# interface.net
KiCad netlist of a schematic drawn in Altium Designer
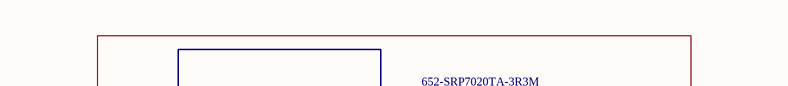
[diagram p0: interface.SchDoc, top left]
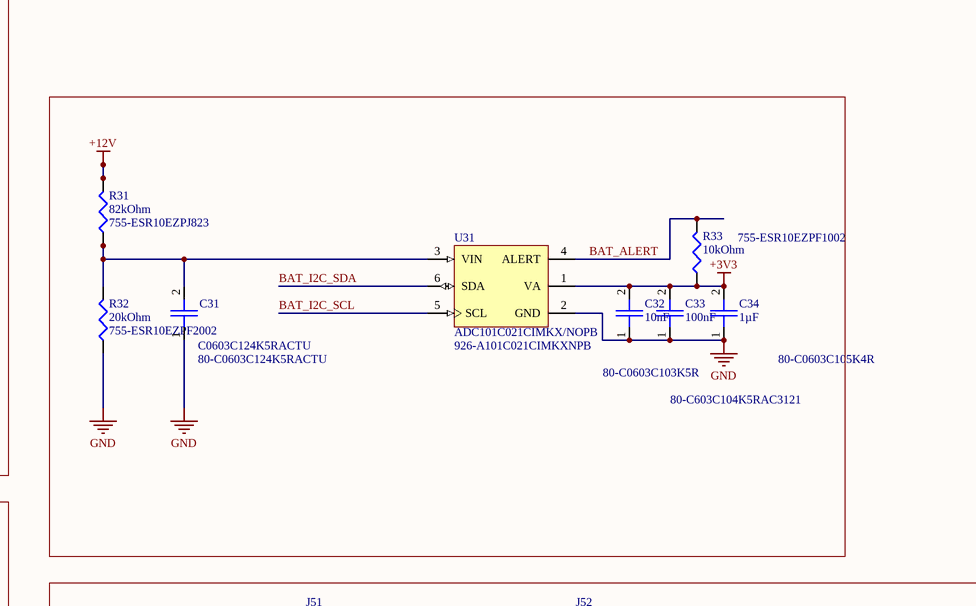
[diagram p1: interface.SchDoc, top right]
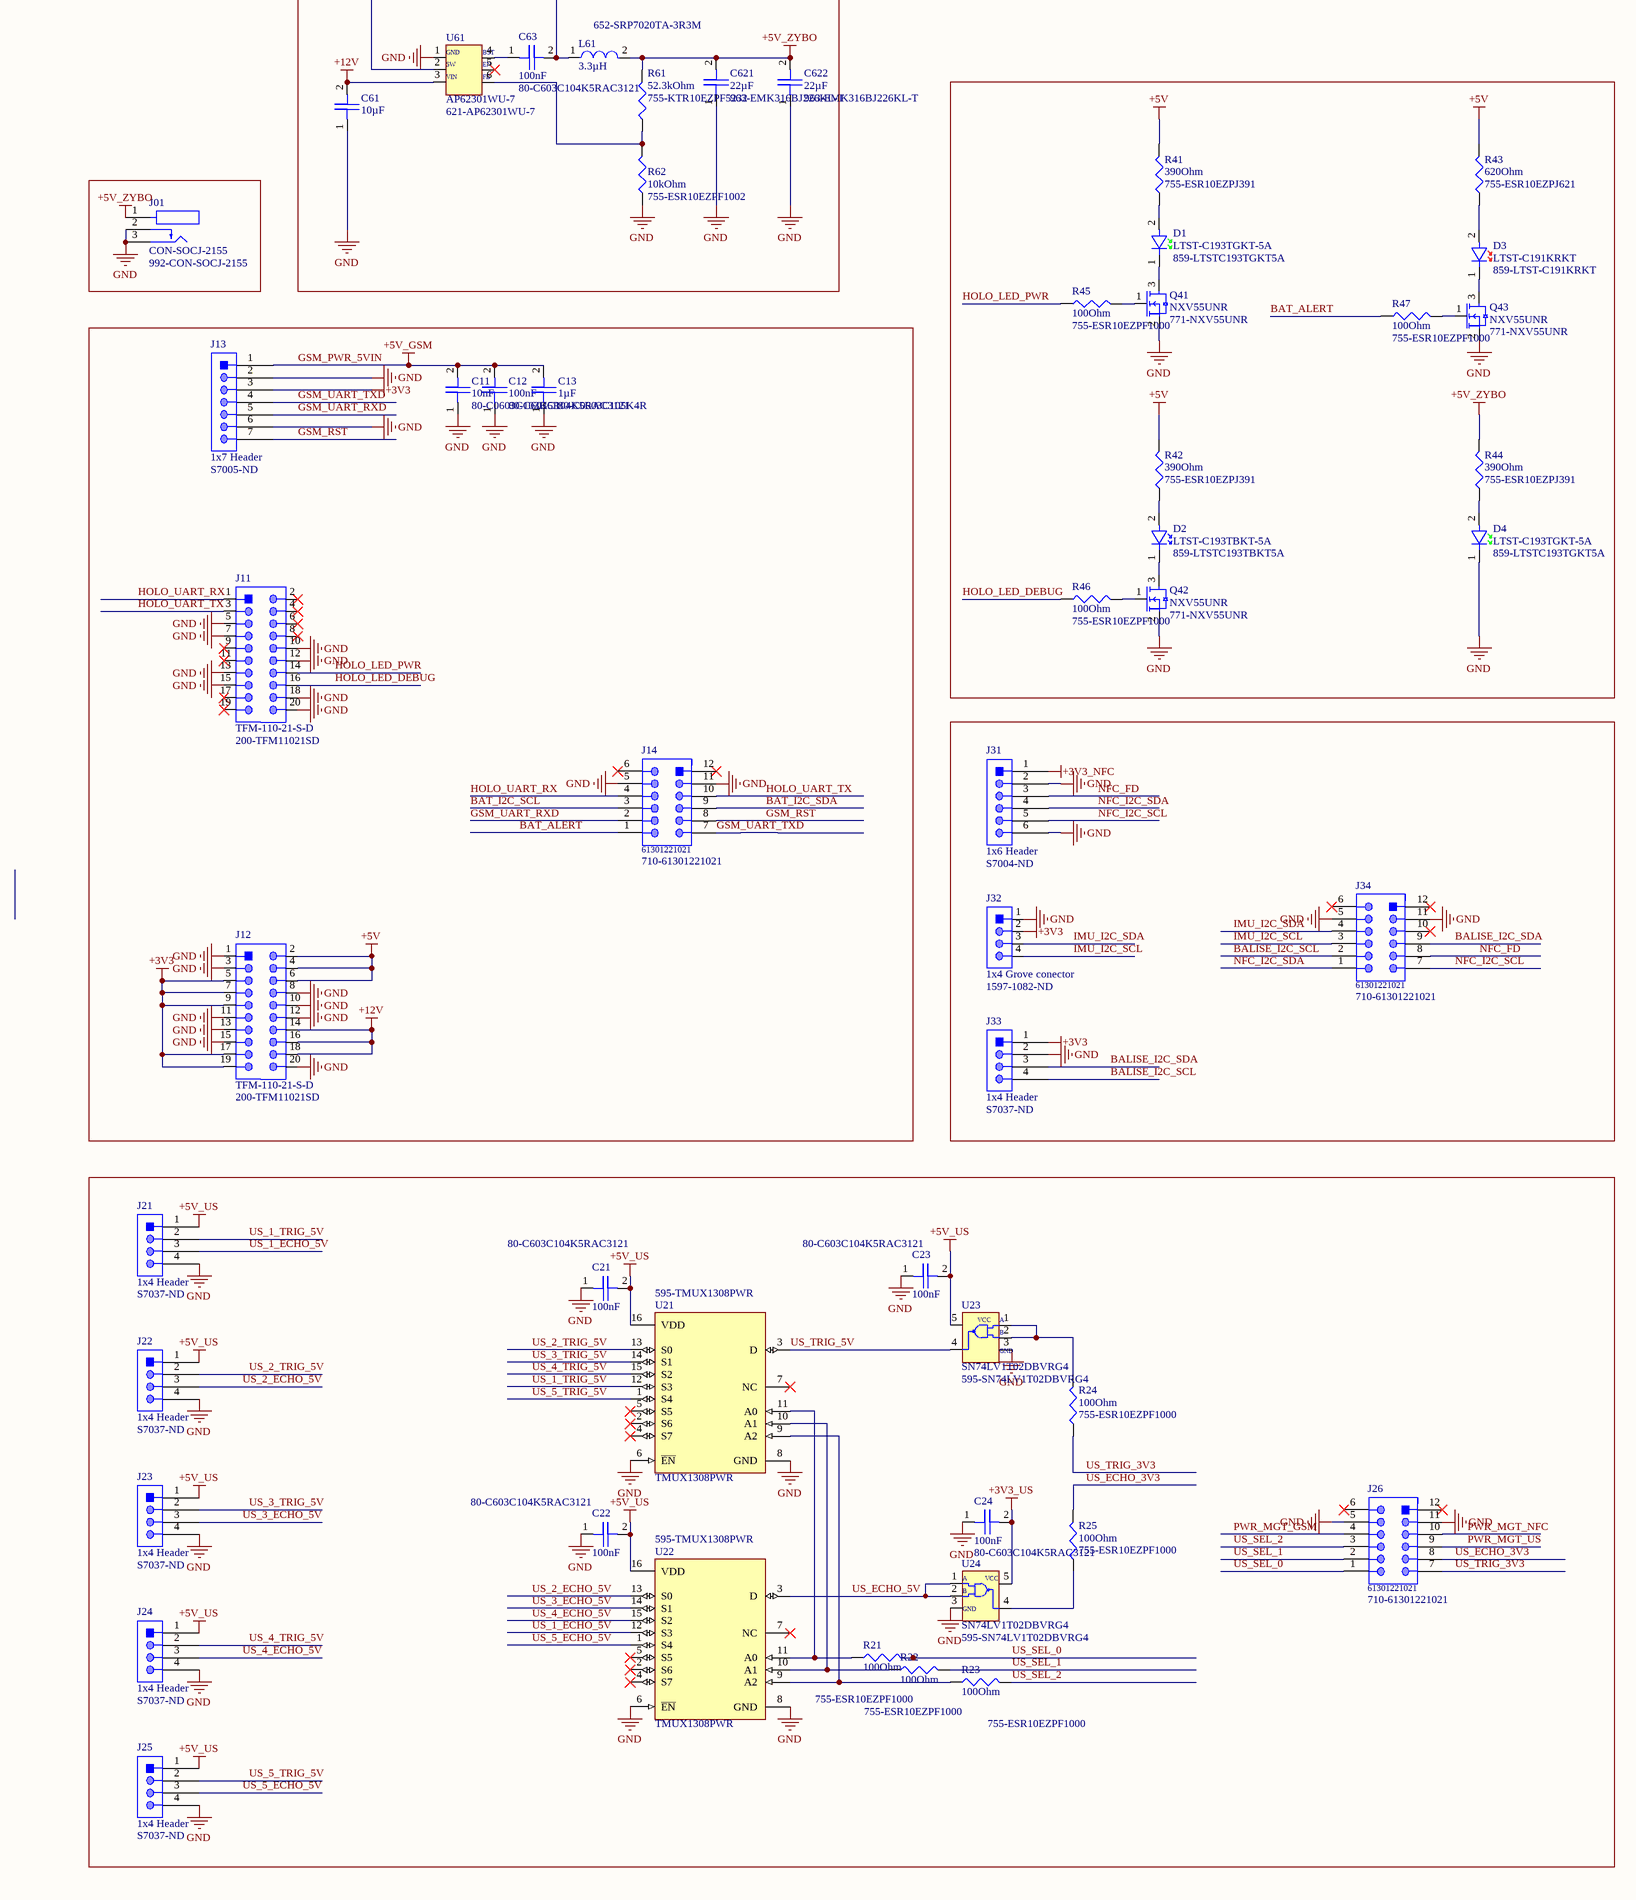
[diagram p2: interface.SchDoc, bottom left]
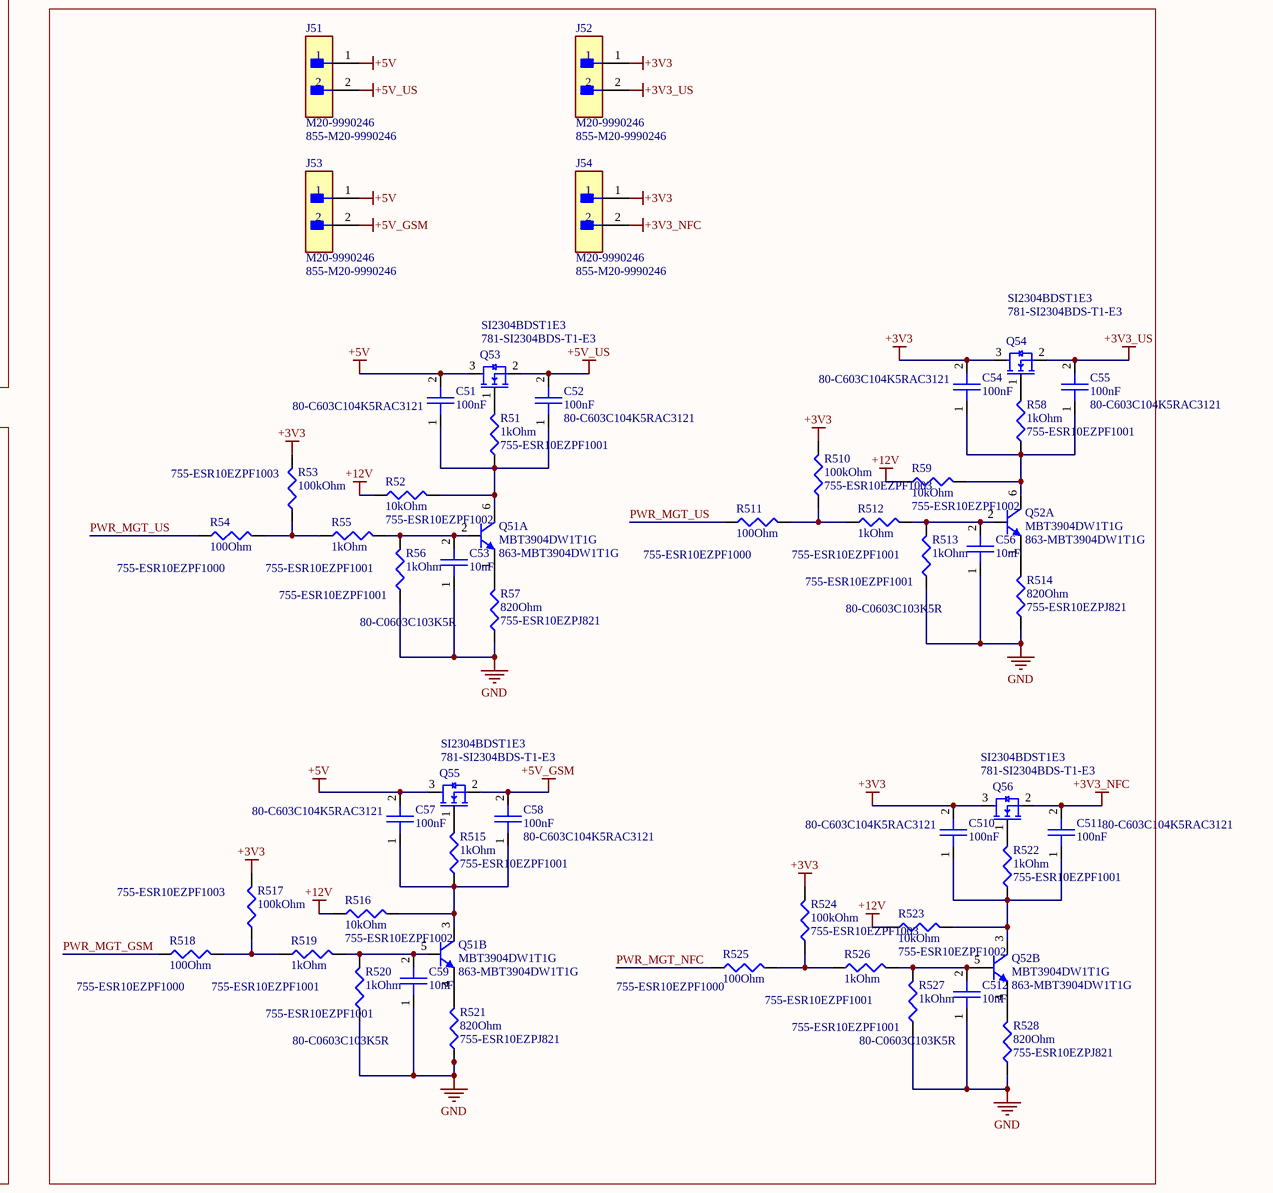
[diagram p3: interface.SchDoc, bottom right]

(export (version "E")
  (design (tool "Eeschema 10.0.6"))
  (components
    (comp (ref "C11")
      (value "10nF")
      (footprint "FP-C0603C-CF-IPC_A")
      (description "CAP CER 10000PF 50V X7R 0603")
      (fields
        (field (name "MANUFACTURER") "KEMET")
        (field (name "MANUFACTURER PART NUMBER") "C0603C103K5RACTU")
        (field (name "SUPPLIER PART NUMBER 1") "80-C0603C103K5R")
      )
      (libsource (lib "interface_Schlib") (part "C0603C103K5RACTU"))
    )
    (comp (ref "C12")
      (value "100nF")
      (footprint "FP-C0603C104K5RAC3121-IPC_A")
      (description "Cap Ceramic 0.1uF 50V X7R 10% Pad SMD 0603 125°C T/R")
      (fields
        (field (name "MANUFACTURER") "KEMET")
        (field (name "MANUFACTURER PART NUMBER") "C0603C104K5RAC3121")
        (field (name "SUPPLIER PART NUMBER 1") "80-C603C104K5RAC3121")
      )
      (libsource (lib "interface_Schlib") (part "C0603C104K5RAC3121"))
    )
    (comp (ref "C13")
      (value "1µF")
      (footprint "CAPC1608X90X35NL15T15")
      (description "Cap Ceramic 1uF 16V X7R 10% SMD 0603 125°C Paper T/R")
      (fields
        (field (name "MANUFACTURER") "KEMET")
        (field (name "MANUFACTURER PART NUMBER") "C0603C105K4RACTU")
        (field (name "SUPPLIER PART NUMBER 1") "80-C0603C105K4R")
      )
      (libsource (lib "interface_Schlib") (part "C0603C105K4RACTU"))
    )
    (comp (ref "C21")
      (value "100nF")
      (footprint "FP-C0603C104K5RAC3121-IPC_A")
      (description "Cap Ceramic 0.1uF 50V X7R 10% Pad SMD 0603 125°C T/R")
      (fields
        (field (name "MANUFACTURER") "KEMET")
        (field (name "MANUFACTURER PART NUMBER") "C0603C104K5RAC3121")
        (field (name "SUPPLIER PART NUMBER 1") "80-C603C104K5RAC3121")
      )
      (libsource (lib "interface_Schlib") (part "C0603C104K5RAC3121"))
    )
    (comp (ref "C22")
      (value "100nF")
      (footprint "FP-C0603C104K5RAC3121-IPC_A")
      (description "Cap Ceramic 0.1uF 50V X7R 10% Pad SMD 0603 125°C T/R")
      (fields
        (field (name "MANUFACTURER") "KEMET")
        (field (name "MANUFACTURER PART NUMBER") "C0603C104K5RAC3121")
        (field (name "SUPPLIER PART NUMBER 1") "80-C603C104K5RAC3121")
      )
      (libsource (lib "interface_Schlib") (part "C0603C104K5RAC3121"))
    )
    (comp (ref "C23")
      (value "100nF")
      (footprint "FP-C0603C104K5RAC3121-IPC_A")
      (description "Cap Ceramic 0.1uF 50V X7R 10% Pad SMD 0603 125°C T/R")
      (fields
        (field (name "MANUFACTURER") "KEMET")
        (field (name "MANUFACTURER PART NUMBER") "C0603C104K5RAC3121")
        (field (name "SUPPLIER PART NUMBER 1") "80-C603C104K5RAC3121")
      )
      (libsource (lib "interface_Schlib") (part "C0603C104K5RAC3121"))
    )
    (comp (ref "C24")
      (value "100nF")
      (footprint "FP-C0603C104K5RAC3121-IPC_A")
      (description "Cap Ceramic 0.1uF 50V X7R 10% Pad SMD 0603 125°C T/R")
      (fields
        (field (name "MANUFACTURER") "KEMET")
        (field (name "MANUFACTURER PART NUMBER") "C0603C104K5RAC3121")
        (field (name "SUPPLIER PART NUMBER 1") "80-C603C104K5RAC3121")
      )
      (libsource (lib "interface_Schlib") (part "C0603C104K5RAC3121"))
    )
    (comp (ref "C31")
      (value "C0603C124K5RACTU")
      (footprint "FP-C0603C-CF-IPC_A")
      (description "0603 C 120nF Ceramic Multilayer Capacitor; 50 V; +125degC; X7R Dielec; +/-10%")
      (fields
        (field (name "MANUFACTURER") "KEMET")
        (field (name "TOLERANCE") "10%")
        (field (name "SUPPLIER PART NUMBER 1") "80-C0603C124K5RACTU")
      )
      (libsource (lib "interface_Schlib") (part "C0603C124K5RACTU"))
    )
    (comp (ref "C32")
      (value "10nF")
      (footprint "FP-C0603C-CF-IPC_A")
      (description "CAP CER 10000PF 50V X7R 0603")
      (fields
        (field (name "MANUFACTURER") "KEMET")
        (field (name "MANUFACTURER PART NUMBER") "C0603C103K5RACTU")
        (field (name "SUPPLIER PART NUMBER 1") "80-C0603C103K5R")
      )
      (libsource (lib "interface_Schlib") (part "C0603C103K5RACTU"))
    )
    (comp (ref "C33")
      (value "100nF")
      (footprint "FP-C0603C104K5RAC3121-IPC_A")
      (description "Cap Ceramic 0.1uF 50V X7R 10% Pad SMD 0603 125°C T/R")
      (fields
        (field (name "MANUFACTURER") "KEMET")
        (field (name "MANUFACTURER PART NUMBER") "C0603C104K5RAC3121")
        (field (name "SUPPLIER PART NUMBER 1") "80-C603C104K5RAC3121")
      )
      (libsource (lib "interface_Schlib") (part "C0603C104K5RAC3121"))
    )
    (comp (ref "C34")
      (value "1µF")
      (footprint "CAPC1608X90X35NL15T15")
      (description "Cap Ceramic 1uF 16V X7R 10% SMD 0603 125°C Paper T/R")
      (fields
        (field (name "MANUFACTURER") "KEMET")
        (field (name "MANUFACTURER PART NUMBER") "C0603C105K4RACTU")
        (field (name "SUPPLIER PART NUMBER 1") "80-C0603C105K4R")
      )
      (libsource (lib "interface_Schlib") (part "C0603C105K4RACTU"))
    )
    (comp (ref "C51")
      (value "100nF")
      (footprint "FP-C0603C104K5RAC3121-IPC_A")
      (description "Cap Ceramic 0.1uF 50V X7R 10% Pad SMD 0603 125°C T/R")
      (fields
        (field (name "MANUFACTURER") "KEMET")
        (field (name "MANUFACTURER PART NUMBER") "C0603C104K5RAC3121")
        (field (name "SUPPLIER PART NUMBER 1") "80-C603C104K5RAC3121")
      )
      (libsource (lib "interface_Schlib") (part "C0603C104K5RAC3121"))
    )
    (comp (ref "C52")
      (value "100nF")
      (footprint "FP-C0603C104K5RAC3121-IPC_A")
      (description "Cap Ceramic 0.1uF 50V X7R 10% Pad SMD 0603 125°C T/R")
      (fields
        (field (name "MANUFACTURER") "KEMET")
        (field (name "MANUFACTURER PART NUMBER") "C0603C104K5RAC3121")
        (field (name "SUPPLIER PART NUMBER 1") "80-C603C104K5RAC3121")
      )
      (libsource (lib "interface_Schlib") (part "C0603C104K5RAC3121"))
    )
    (comp (ref "C53")
      (value "10nF")
      (footprint "FP-C0603C-CF-IPC_A")
      (description "CAP CER 10000PF 50V X7R 0603")
      (fields
        (field (name "MANUFACTURER") "KEMET")
        (field (name "MANUFACTURER PART NUMBER") "C0603C103K5RACTU")
        (field (name "SUPPLIER PART NUMBER 1") "80-C0603C103K5R")
      )
      (libsource (lib "interface_Schlib") (part "C0603C103K5RACTU"))
    )
    (comp (ref "C54")
      (value "100nF")
      (footprint "FP-C0603C104K5RAC3121-IPC_A")
      (description "Cap Ceramic 0.1uF 50V X7R 10% Pad SMD 0603 125°C T/R")
      (fields
        (field (name "MANUFACTURER") "KEMET")
        (field (name "MANUFACTURER PART NUMBER") "C0603C104K5RAC3121")
        (field (name "SUPPLIER PART NUMBER 1") "80-C603C104K5RAC3121")
      )
      (libsource (lib "interface_Schlib") (part "C0603C104K5RAC3121"))
    )
    (comp (ref "C55")
      (value "100nF")
      (footprint "FP-C0603C104K5RAC3121-IPC_A")
      (description "Cap Ceramic 0.1uF 50V X7R 10% Pad SMD 0603 125°C T/R")
      (fields
        (field (name "MANUFACTURER") "KEMET")
        (field (name "MANUFACTURER PART NUMBER") "C0603C104K5RAC3121")
        (field (name "SUPPLIER PART NUMBER 1") "80-C603C104K5RAC3121")
      )
      (libsource (lib "interface_Schlib") (part "C0603C104K5RAC3121"))
    )
    (comp (ref "C56")
      (value "10nF")
      (footprint "FP-C0603C-CF-IPC_A")
      (description "CAP CER 10000PF 50V X7R 0603")
      (fields
        (field (name "MANUFACTURER") "KEMET")
        (field (name "MANUFACTURER PART NUMBER") "C0603C103K5RACTU")
        (field (name "SUPPLIER PART NUMBER 1") "80-C0603C103K5R")
      )
      (libsource (lib "interface_Schlib") (part "C0603C103K5RACTU"))
    )
    (comp (ref "C57")
      (value "100nF")
      (footprint "FP-C0603C104K5RAC3121-IPC_A")
      (description "Cap Ceramic 0.1uF 50V X7R 10% Pad SMD 0603 125°C T/R")
      (fields
        (field (name "MANUFACTURER") "KEMET")
        (field (name "MANUFACTURER PART NUMBER") "C0603C104K5RAC3121")
        (field (name "SUPPLIER PART NUMBER 1") "80-C603C104K5RAC3121")
      )
      (libsource (lib "interface_Schlib") (part "C0603C104K5RAC3121"))
    )
    (comp (ref "C58")
      (value "100nF")
      (footprint "FP-C0603C104K5RAC3121-IPC_A")
      (description "Cap Ceramic 0.1uF 50V X7R 10% Pad SMD 0603 125°C T/R")
      (fields
        (field (name "MANUFACTURER") "KEMET")
        (field (name "MANUFACTURER PART NUMBER") "C0603C104K5RAC3121")
        (field (name "SUPPLIER PART NUMBER 1") "80-C603C104K5RAC3121")
      )
      (libsource (lib "interface_Schlib") (part "C0603C104K5RAC3121"))
    )
    (comp (ref "C59")
      (value "10nF")
      (footprint "FP-C0603C-CF-IPC_A")
      (description "CAP CER 10000PF 50V X7R 0603")
      (fields
        (field (name "MANUFACTURER") "KEMET")
        (field (name "MANUFACTURER PART NUMBER") "C0603C103K5RACTU")
        (field (name "SUPPLIER PART NUMBER 1") "80-C0603C103K5R")
      )
      (libsource (lib "interface_Schlib") (part "C0603C103K5RACTU"))
    )
    (comp (ref "C61")
      (value "10µF")
      (footprint "FP-1206-L_3_2_0_15-W_1_6-IPC_A")
      (description "Capacitor Ceramic 10uF 16V X5R 10% SMD 1206 85°C Embossed T/R")
      (fields
        (field (name "MANUFACTURER") "Taiyo Yuden")
        (field (name "MANUFACTURER PART NUMBER") "EMK316BJ106KL8T")
      )
      (libsource (lib "interface_Schlib") (part "EMK316BJ106KL8T"))
    )
    (comp (ref "C63")
      (value "100nF")
      (footprint "FP-C0603C104K5RAC3121-IPC_A")
      (description "Cap Ceramic 0.1uF 50V X7R 10% Pad SMD 0603 125°C T/R")
      (fields
        (field (name "MANUFACTURER") "KEMET")
        (field (name "MANUFACTURER PART NUMBER") "C0603C104K5RAC3121")
        (field (name "SUPPLIER PART NUMBER 1") "80-C603C104K5RAC3121")
      )
      (libsource (lib "interface_Schlib") (part "C0603C104K5RAC3121"))
    )
    (comp (ref "C510")
      (value "100nF")
      (footprint "FP-C0603C104K5RAC3121-IPC_A")
      (description "Cap Ceramic 0.1uF 50V X7R 10% Pad SMD 0603 125°C T/R")
      (fields
        (field (name "MANUFACTURER") "KEMET")
        (field (name "MANUFACTURER PART NUMBER") "C0603C104K5RAC3121")
        (field (name "SUPPLIER PART NUMBER 1") "80-C603C104K5RAC3121")
      )
      (libsource (lib "interface_Schlib") (part "C0603C104K5RAC3121"))
    )
    (comp (ref "C511")
      (value "100nF")
      (footprint "FP-C0603C104K5RAC3121-IPC_A")
      (description "Cap Ceramic 0.1uF 50V X7R 10% Pad SMD 0603 125°C T/R")
      (fields
        (field (name "MANUFACTURER") "KEMET")
        (field (name "MANUFACTURER PART NUMBER") "C0603C104K5RAC3121")
        (field (name "SUPPLIER PART NUMBER 1") "80-C603C104K5RAC3121")
      )
      (libsource (lib "interface_Schlib") (part "C0603C104K5RAC3121"))
    )
    (comp (ref "C512")
      (value "10nF")
      (footprint "FP-C0603C-CF-IPC_A")
      (description "CAP CER 10000PF 50V X7R 0603")
      (fields
        (field (name "MANUFACTURER") "KEMET")
        (field (name "MANUFACTURER PART NUMBER") "C0603C103K5RACTU")
        (field (name "SUPPLIER PART NUMBER 1") "80-C0603C103K5R")
      )
      (libsource (lib "interface_Schlib") (part "C0603C103K5RACTU"))
    )
    (comp (ref "C621")
      (value "22µF")
      (footprint "CAPC3216X180N")
      (description "Cap Ceramic 22uF 16V X7R 10% SMD 0805 125°C Paper T/R")
      (fields
        (field (name "MANUFACTURER") "Taiyo Yuden")
        (field (name "MANUFACTURER PART NUMBER") "EMK316BJ226KL-T")
        (field (name "SUPPLIER PART NUMBER 1") "963-EMK316BJ226KL-T")
      )
      (libsource (lib "interface_Schlib") (part "EMK316BJ226KL-T"))
    )
    (comp (ref "C622")
      (value "22µF")
      (footprint "CAPC3216X180N")
      (description "Cap Ceramic 22uF 16V X7R 10% SMD 0805 125°C Paper T/R")
      (fields
        (field (name "MANUFACTURER") "Taiyo Yuden")
        (field (name "MANUFACTURER PART NUMBER") "EMK316BJ226KL-T")
        (field (name "SUPPLIER PART NUMBER 1") "963-EMK316BJ226KL-T")
      )
      (libsource (lib "interface_Schlib") (part "EMK316BJ226KL-T"))
    )
    (comp (ref "D1")
      (value "LTST-C193TGKT-5A")
      (footprint "FP-LTST-C193TGKT-5A")
      (description "0603(H=0.35mm) 绿色 λD=520nm~535nm VR=5V VF=2.5V~3.1V IF=5mA PD=76mW")
      (fields
        (field (name "MANUFACTURER") "Vishay Lite-On")
        (field (name "SUPPLIER PART NUMBER 1") "859-LTSTC193TGKT5A")
      )
      (libsource (lib "interface_Schlib") (part "LTST-C193TGKT-5A"))
    )
    (comp (ref "D2")
      (value "LTST-C193TBKT-5A")
      (footprint "FP-LTST-C193TBKT-5A-MFG")
      (description "0603(H=0.35mm) 蓝色 λD=465nm~475nm VR=5V VF=2.65V~3.05V IF=5mA PD=76mW")
      (fields
        (field (name "MANUFACTURER") "Vishay Lite-On")
        (field (name "SUPPLIER PART NUMBER 1") "859-LTSTC193TBKT5A")
      )
      (libsource (lib "interface_Schlib") (part "LTST-C193TBKT-5A"))
    )
    (comp (ref "D3")
      (value "LTST-C191KRKT")
      (footprint "FP-LTST-C191KRKT")
      (description "0603(H=0.65mm) 红色 λD=631nm VR=5V VF=2.0V~2.4V IF=20mA PD=75mW")
      (fields
        (field (name "MANUFACTURER") "Vishay Lite-On")
        (field (name "SUPPLIER PART NUMBER 1") "859-LTST-C191KRKT")
        (field (name "VOLTAGE") "2V")
      )
      (libsource (lib "interface_Schlib") (part "LTST-C191KRKT"))
    )
    (comp (ref "D4")
      (value "LTST-C193TGKT-5A")
      (footprint "FP-LTST-C193TGKT-5A")
      (description "0603(H=0.35mm) 绿色 λD=520nm~535nm VR=5V VF=2.5V~3.1V IF=5mA PD=76mW")
      (fields
        (field (name "MANUFACTURER") "Vishay Lite-On")
        (field (name "SUPPLIER PART NUMBER 1") "859-LTSTC193TGKT5A")
      )
      (libsource (lib "interface_Schlib") (part "LTST-C193TGKT-5A"))
    )
    (comp (ref "J01")
      (value "CON-SOCJ-2155")
      (footprint "GRAVITECH_CON-SOCJ-2155")
      (description "DC Power Connectors Power Jack/Connector 2.1mm x 5.5mm")
      (fields
        (field (name "MANUFACTURER") "Gravitech")
        (field (name "SUPPLIER PART NUMBER 1") "992-CON-SOCJ-2155")
      )
      (libsource (lib "interface_Schlib") (part "CON-SOCJ-2155"))
    )
    (comp (ref "J11")
      (value "TFM-110-21-S-D")
      (footprint "SAMTEC_TFM-110-21-S-D")
      (fields (field (name "MANUFACTURER") "Samtec") (field (name "SUPPLIER PART NUMBER 1") "200-TFM11021SD"))
      (libsource (lib "interface_Schlib") (part "TFM-110-21-S-D"))
    )
    (comp (ref "J12")
      (value "TFM-110-21-S-D")
      (footprint "SAMTEC_TFM-110-21-S-D")
      (fields (field (name "MANUFACTURER") "Samtec") (field (name "SUPPLIER PART NUMBER 1") "200-TFM11021SD"))
      (libsource (lib "interface_Schlib") (part "TFM-110-21-S-D"))
    )
    (comp (ref "J13")
      (value "1x7 Header")
      (footprint "header 1x7")
      (description "Female, 7C, Straight, .100\"CC; 3.20mm Tail, No Mt. 100u\" Tin; PBT, Phos Bronze, 105 C")
      (fields
        (field (name "MANUFACTURER") "Sullins")
        (field (name "MANUFACTURER PART NUMBER") "PPTC071LFBN-RC")
        (field (name "SUPPLIER PART NUMBER 1") "S7005-ND")
      )
      (libsource (lib "interface_Schlib") (part "PPTC071LFBN-RC"))
    )
    (comp (ref "J14")
      (value "61301221021")
      (footprint "61301221021")
      (description "THT Angled Pin Header WR-PHD, Pitch 2.54 mm, Dual Row, 12 pins")
      (fields
        (field (name "MANUFACTURER") "Wurth Elektronik")
        (field (name "SUPPLIER PART NUMBER 1") "710-61301221021")
        (field (name "PUBLISHER") "WurthElektronik")
      )
      (libsource (lib "interface_Schlib") (part "61301221021"))
    )
    (comp (ref "J21")
      (value "1x4 Header")
      (footprint "header 1x4")
      (description "4 Positions Embase Connecteur 0,100 po (2,54mm) Trou traversant Or")
      (fields
        (field (name "MANUFACTURER") "Sullins")
        (field (name "MANUFACTURER PART NUMBER") "PPPC041LFBN-RC")
        (field (name "SUPPLIER PART NUMBER 1") "S7037-ND")
      )
      (libsource (lib "interface_Schlib") (part "PPPC041LFBN-RC"))
    )
    (comp (ref "J22")
      (value "1x4 Header")
      (footprint "header 1x4")
      (description "4 Positions Embase Connecteur 0,100 po (2,54mm) Trou traversant Or")
      (fields
        (field (name "MANUFACTURER") "Sullins")
        (field (name "MANUFACTURER PART NUMBER") "PPPC041LFBN-RC")
        (field (name "SUPPLIER PART NUMBER 1") "S7037-ND")
      )
      (libsource (lib "interface_Schlib") (part "PPPC041LFBN-RC"))
    )
    (comp (ref "J23")
      (value "1x4 Header")
      (footprint "header 1x4")
      (description "4 Positions Embase Connecteur 0,100 po (2,54mm) Trou traversant Or")
      (fields
        (field (name "MANUFACTURER") "Sullins")
        (field (name "MANUFACTURER PART NUMBER") "PPPC041LFBN-RC")
        (field (name "SUPPLIER PART NUMBER 1") "S7037-ND")
      )
      (libsource (lib "interface_Schlib") (part "PPPC041LFBN-RC"))
    )
    (comp (ref "J24")
      (value "1x4 Header")
      (footprint "header 1x4")
      (description "4 Positions Embase Connecteur 0,100 po (2,54mm) Trou traversant Or")
      (fields
        (field (name "MANUFACTURER") "Sullins")
        (field (name "MANUFACTURER PART NUMBER") "PPPC041LFBN-RC")
        (field (name "SUPPLIER PART NUMBER 1") "S7037-ND")
      )
      (libsource (lib "interface_Schlib") (part "PPPC041LFBN-RC"))
    )
    (comp (ref "J25")
      (value "1x4 Header")
      (footprint "header 1x4")
      (description "4 Positions Embase Connecteur 0,100 po (2,54mm) Trou traversant Or")
      (fields
        (field (name "MANUFACTURER") "Sullins")
        (field (name "MANUFACTURER PART NUMBER") "PPPC041LFBN-RC")
        (field (name "SUPPLIER PART NUMBER 1") "S7037-ND")
      )
      (libsource (lib "interface_Schlib") (part "PPPC041LFBN-RC"))
    )
    (comp (ref "J26")
      (value "61301221021")
      (footprint "61301221021")
      (description "THT Angled Pin Header WR-PHD, Pitch 2.54 mm, Dual Row, 12 pins")
      (fields
        (field (name "MANUFACTURER") "Wurth Elektronik")
        (field (name "SUPPLIER PART NUMBER 1") "710-61301221021")
        (field (name "PUBLISHER") "WurthElektronik")
      )
      (libsource (lib "interface_Schlib") (part "61301221021"))
    )
    (comp (ref "J31")
      (value "1x6 Header")
      (footprint "header 1x6")
      (description "Female, 6 C, Straight, .100\"CC; 3.20mm Tail, No Mt. 100u\" Tin; PBT, Phos Bronze, 105 C")
      (fields
        (field (name "MANUFACTURER") "Sullins")
        (field (name "MANUFACTURER PART NUMBER") "PPTC061LFBN-RC")
        (field (name "SUPPLIER PART NUMBER 1") "S7004-ND")
      )
      (libsource (lib "interface_Schlib") (part "PPTC061LFBN-RC"))
    )
    (comp (ref "J32")
      (value "1x4 Grove conector")
      (footprint "FP-110990030")
      (description "Grove - Universal 4 pin connector [Seeed Studio] 110990030 Grove - Universal 4 pin connector")
      (fields
        (field (name "MANUFACTURER") "Seeed Studio")
        (field (name "MANUFACTURER PART NUMBER") "110990030")
        (field (name "SUPPLIER PART NUMBER 1") "1597-1082-ND")
      )
      (libsource (lib "interface_Schlib") (part "110990030"))
    )
    (comp (ref "J33")
      (value "1x4 Header")
      (footprint "header 1x4")
      (description "4 Positions Embase Connecteur 0,100 po (2,54mm) Trou traversant Or")
      (fields
        (field (name "MANUFACTURER") "Sullins")
        (field (name "MANUFACTURER PART NUMBER") "PPPC041LFBN-RC")
        (field (name "SUPPLIER PART NUMBER 1") "S7037-ND")
      )
      (libsource (lib "interface_Schlib") (part "PPPC041LFBN-RC"))
    )
    (comp (ref "J34")
      (value "61301221021")
      (footprint "61301221021")
      (description "THT Angled Pin Header WR-PHD, Pitch 2.54 mm, Dual Row, 12 pins")
      (fields
        (field (name "MANUFACTURER") "Wurth Elektronik")
        (field (name "SUPPLIER PART NUMBER 1") "710-61301221021")
        (field (name "PUBLISHER") "WurthElektronik")
      )
      (libsource (lib "interface_Schlib") (part "61301221021"))
    )
    (comp (ref "J51")
      (value "M20-9990246")
      (footprint "FP-M20-9990246-MFG")
      (description "2.54mm (0.1\") Pitch SIL Vertical PC Tail Pin Header, 6.1mm mating pin height, tin, 2 contacts")
      (fields
        (field (name "MANUFACTURER") "Harwin")
        (field (name "SUPPLIER PART NUMBER 1") "855-M20-9990246")
      )
      (libsource (lib "interface_Schlib") (part "M20-9990246"))
    )
    (comp (ref "J52")
      (value "M20-9990246")
      (footprint "FP-M20-9990246-MFG")
      (description "2.54mm (0.1\") Pitch SIL Vertical PC Tail Pin Header, 6.1mm mating pin height, tin, 2 contacts")
      (fields
        (field (name "MANUFACTURER") "Harwin")
        (field (name "SUPPLIER PART NUMBER 1") "855-M20-9990246")
      )
      (libsource (lib "interface_Schlib") (part "M20-9990246"))
    )
    (comp (ref "J53")
      (value "M20-9990246")
      (footprint "FP-M20-9990246-MFG")
      (description "2.54mm (0.1\") Pitch SIL Vertical PC Tail Pin Header, 6.1mm mating pin height, tin, 2 contacts")
      (fields
        (field (name "MANUFACTURER") "Harwin")
        (field (name "SUPPLIER PART NUMBER 1") "855-M20-9990246")
      )
      (libsource (lib "interface_Schlib") (part "M20-9990246"))
    )
    (comp (ref "J54")
      (value "M20-9990246")
      (footprint "FP-M20-9990246-MFG")
      (description "2.54mm (0.1\") Pitch SIL Vertical PC Tail Pin Header, 6.1mm mating pin height, tin, 2 contacts")
      (fields
        (field (name "MANUFACTURER") "Harwin")
        (field (name "SUPPLIER PART NUMBER 1") "855-M20-9990246")
      )
      (libsource (lib "interface_Schlib") (part "M20-9990246"))
    )
    (comp (ref "L61")
      (value "3.3µH")
      (footprint "INDC7066X20N")
      (fields
        (field (name "MANUFACTURER") "Bourns")
        (field (name "MANUFACTURER PART NUMBER") "SRP7020TA-3R3M")
        (field (name "SUPPLIER PART NUMBER 1") "652-SRP7020TA-3R3M")
      )
      (libsource (lib "interface_Schlib") (part "SRP7020TA-3R3M"))
    )
    (comp (ref "Q41")
      (value "NXV55UNR")
      (footprint "SOT95P230X110-3N")
      (description "Transistor MOSFET N-Channel 30V 2.3A 3-Pin SOT-23")
      (fields (field (name "MANUFACTURER") "Nexperia") (field (name "SUPPLIER PART NUMBER 1") "771-NXV55UNR"))
      (libsource (lib "interface_Schlib") (part "NXV55UNR"))
    )
    (comp (ref "Q42")
      (value "NXV55UNR")
      (footprint "SOT95P230X110-3N")
      (description "Transistor MOSFET N-Channel 30V 2.3A 3-Pin SOT-23")
      (fields (field (name "MANUFACTURER") "Nexperia") (field (name "SUPPLIER PART NUMBER 1") "771-NXV55UNR"))
      (libsource (lib "interface_Schlib") (part "NXV55UNR"))
    )
    (comp (ref "Q43")
      (value "NXV55UNR")
      (footprint "SOT95P230X110-3N")
      (description "Transistor MOSFET N-Channel 30V 2.3A 3-Pin SOT-23")
      (fields (field (name "MANUFACTURER") "Nexperia") (field (name "SUPPLIER PART NUMBER 1") "771-NXV55UNR"))
      (libsource (lib "interface_Schlib") (part "NXV55UNR"))
    )
    (comp (ref "Q51")
      (value "MBT3904DW1T1G")
      (footprint "ONSC-SOT-363-6-419B-02_W_V")
      (description "Dual General Purpose Transistors, 6-Pin SOT-363, Pb-Free, Tape and Reel")
      (fields
        (field (name "MANUFACTURER") "On Semiconductor")
        (field (name "SUPPLIER PART NUMBER 1") "863-MBT3904DW1T1G")
      )
      (libsource (lib "interface_Schlib") (part "CMP-1048-00877-1"))
    )
    (comp (ref "Q52")
      (value "MBT3904DW1T1G")
      (footprint "ONSC-SOT-363-6-419B-02_W_V")
      (description "Dual General Purpose Transistors, 6-Pin SOT-363, Pb-Free, Tape and Reel")
      (fields
        (field (name "MANUFACTURER") "On Semiconductor")
        (field (name "SUPPLIER PART NUMBER 1") "863-MBT3904DW1T1G")
      )
      (libsource (lib "interface_Schlib") (part "CMP-1048-00877-1"))
    )
    (comp (ref "Q53")
      (value "SI2304BDST1E3")
      (footprint "FP-SI2304BDST1E3")
      (description "Single N-Channel 30 V 0.07 Ohms Surface Mount Power Mosfet - SOT-23")
      (fields
        (field (name "MANUFACTURER") "Vishay")
        (field (name "SUPPLIER PART NUMBER 1") "781-SI2304BDS-T1-E3")
      )
      (libsource (lib "interface_Schlib") (part "SI2304BDST1E3"))
    )
    (comp (ref "Q54")
      (value "SI2304BDST1E3")
      (footprint "FP-SI2304BDST1E3")
      (description "Single N-Channel 30 V 0.07 Ohms Surface Mount Power Mosfet - SOT-23")
      (fields
        (field (name "MANUFACTURER") "Vishay")
        (field (name "SUPPLIER PART NUMBER 1") "781-SI2304BDS-T1-E3")
      )
      (libsource (lib "interface_Schlib") (part "SI2304BDST1E3"))
    )
    (comp (ref "Q55")
      (value "SI2304BDST1E3")
      (footprint "FP-SI2304BDST1E3")
      (description "Single N-Channel 30 V 0.07 Ohms Surface Mount Power Mosfet - SOT-23")
      (fields
        (field (name "MANUFACTURER") "Vishay")
        (field (name "SUPPLIER PART NUMBER 1") "781-SI2304BDS-T1-E3")
      )
      (libsource (lib "interface_Schlib") (part "SI2304BDST1E3"))
    )
    (comp (ref "Q56")
      (value "SI2304BDST1E3")
      (footprint "FP-SI2304BDST1E3")
      (description "Single N-Channel 30 V 0.07 Ohms Surface Mount Power Mosfet - SOT-23")
      (fields
        (field (name "MANUFACTURER") "Vishay")
        (field (name "SUPPLIER PART NUMBER 1") "781-SI2304BDS-T1-E3")
      )
      (libsource (lib "interface_Schlib") (part "SI2304BDST1E3"))
    )
    (comp (ref "R21")
      (value "100Ohm")
      (footprint "FP-ESR10-IPC_A")
      (description "Res Thick Film 0805 100 Ohm 1% 2/5W ±100ppm/°C Molded SMD Paper T/R")
      (fields
        (field (name "MANUFACTURER") "Rohm")
        (field (name "MANUFACTURER PART NUMBER") "ESR10EZPF1000")
        (field (name "SUPPLIER PART NUMBER 1") "755-ESR10EZPF1000")
      )
      (libsource (lib "interface_Schlib") (part "ESR10EZPF1000"))
    )
    (comp (ref "R22")
      (value "100Ohm")
      (footprint "FP-ESR10-IPC_A")
      (description "Res Thick Film 0805 100 Ohm 1% 2/5W ±100ppm/°C Molded SMD Paper T/R")
      (fields
        (field (name "MANUFACTURER") "Rohm")
        (field (name "MANUFACTURER PART NUMBER") "ESR10EZPF1000")
        (field (name "SUPPLIER PART NUMBER 1") "755-ESR10EZPF1000")
      )
      (libsource (lib "interface_Schlib") (part "ESR10EZPF1000"))
    )
    (comp (ref "R23")
      (value "100Ohm")
      (footprint "FP-ESR10-IPC_A")
      (description "Res Thick Film 0805 100 Ohm 1% 2/5W ±100ppm/°C Molded SMD Paper T/R")
      (fields
        (field (name "MANUFACTURER") "Rohm")
        (field (name "MANUFACTURER PART NUMBER") "ESR10EZPF1000")
        (field (name "SUPPLIER PART NUMBER 1") "755-ESR10EZPF1000")
      )
      (libsource (lib "interface_Schlib") (part "ESR10EZPF1000"))
    )
    (comp (ref "R24")
      (value "100Ohm")
      (footprint "FP-ESR10-IPC_A")
      (description "Res Thick Film 0805 100 Ohm 1% 2/5W ±100ppm/°C Molded SMD Paper T/R")
      (fields
        (field (name "MANUFACTURER") "Rohm")
        (field (name "MANUFACTURER PART NUMBER") "ESR10EZPF1000")
        (field (name "SUPPLIER PART NUMBER 1") "755-ESR10EZPF1000")
      )
      (libsource (lib "interface_Schlib") (part "ESR10EZPF1000"))
    )
    (comp (ref "R25")
      (value "100Ohm")
      (footprint "FP-ESR10-IPC_A")
      (description "Res Thick Film 0805 100 Ohm 1% 2/5W ±100ppm/°C Molded SMD Paper T/R")
      (fields
        (field (name "MANUFACTURER") "Rohm")
        (field (name "MANUFACTURER PART NUMBER") "ESR10EZPF1000")
        (field (name "SUPPLIER PART NUMBER 1") "755-ESR10EZPF1000")
      )
      (libsource (lib "interface_Schlib") (part "ESR10EZPF1000"))
    )
    (comp (ref "R31")
      (value "82kOhm")
      (footprint "FP-ESR10-IPC_A")
      (description "Res Anti-surge 0805 82K Ohm 0.4W 5% SMD")
      (fields
        (field (name "MANUFACTURER") "Rohm")
        (field (name "MANUFACTURER PART NUMBER") "ESR10EZPJ823")
        (field (name "SUPPLIER PART NUMBER 1") "755-ESR10EZPJ823")
      )
      (libsource (lib "interface_Schlib") (part "ESR10EZPJ823"))
    )
    (comp (ref "R32")
      (value "20kOhm")
      (footprint "FP-ESR10-IPC_A")
      (description "Res Thick Film 0805 20KOhm 1% 2/5W ±100ppm/°C Molded SMD Paper T/R")
      (fields
        (field (name "MANUFACTURER") "Rohm")
        (field (name "MANUFACTURER PART NUMBER") "ESR10EZPF2002")
        (field (name "SUPPLIER PART NUMBER 1") "755-ESR10EZPF2002")
      )
      (libsource (lib "interface_Schlib") (part "ESR10EZPF2002"))
    )
    (comp (ref "R33")
      (value "10kOhm")
      (footprint "FP-ESR10-IPC_A")
      (description "Res Thick Film 0805 10K Ohm 1% 0.4W ±100ppm/C Pad SMD Automotive T/R")
      (fields
        (field (name "MANUFACTURER") "Rohm")
        (field (name "MANUFACTURER PART NUMBER") "ESR10EZPF1002")
        (field (name "SUPPLIER PART NUMBER 1") "755-ESR10EZPF1002")
      )
      (libsource (lib "interface_Schlib") (part "ESR10EZPF1002"))
    )
    (comp (ref "R41")
      (value "390Ohm")
      (footprint "FP-ESR10-IPC_A")
      (description "Res Thick Film 0805 390 Ohm 5% 0.4W ±200ppm/C Pad SMD Automotive T/R")
      (fields
        (field (name "MANUFACTURER") "Rohm")
        (field (name "MANUFACTURER PART NUMBER") "ESR10EZPJ391")
        (field (name "SUPPLIER PART NUMBER 1") "755-ESR10EZPJ391")
      )
      (libsource (lib "interface_Schlib") (part "ESR10EZPJ391"))
    )
    (comp (ref "R42")
      (value "390Ohm")
      (footprint "FP-ESR10-IPC_A")
      (description "Res Thick Film 0805 390 Ohm 5% 0.4W ±200ppm/C Pad SMD Automotive T/R")
      (fields
        (field (name "MANUFACTURER") "Rohm")
        (field (name "MANUFACTURER PART NUMBER") "ESR10EZPJ391")
        (field (name "SUPPLIER PART NUMBER 1") "755-ESR10EZPJ391")
      )
      (libsource (lib "interface_Schlib") (part "ESR10EZPJ391"))
    )
    (comp (ref "R43")
      (value "620Ohm")
      (footprint "FP-ESR10-IPC_A")
      (description "Res Thick Film 0805 620 Ohm 5% 0.4W ±200ppm/C Pad SMD Automotive T/R")
      (fields
        (field (name "MANUFACTURER") "Rohm")
        (field (name "MANUFACTURER PART NUMBER") "ESR10EZPJ621")
        (field (name "SUPPLIER PART NUMBER 1") "755-ESR10EZPJ621")
      )
      (libsource (lib "interface_Schlib") (part "ESR10EZPJ621"))
    )
    (comp (ref "R44")
      (value "390Ohm")
      (footprint "FP-ESR10-IPC_A")
      (description "Res Thick Film 0805 390 Ohm 5% 0.4W ±200ppm/C Pad SMD Automotive T/R")
      (fields
        (field (name "MANUFACTURER") "Rohm")
        (field (name "MANUFACTURER PART NUMBER") "ESR10EZPJ391")
        (field (name "SUPPLIER PART NUMBER 1") "755-ESR10EZPJ391")
      )
      (libsource (lib "interface_Schlib") (part "ESR10EZPJ391"))
    )
    (comp (ref "R45")
      (value "100Ohm")
      (footprint "FP-ESR10-IPC_A")
      (description "Res Thick Film 0805 100 Ohm 1% 2/5W ±100ppm/°C Molded SMD Paper T/R")
      (fields
        (field (name "MANUFACTURER") "Rohm")
        (field (name "MANUFACTURER PART NUMBER") "ESR10EZPF1000")
        (field (name "SUPPLIER PART NUMBER 1") "755-ESR10EZPF1000")
      )
      (libsource (lib "interface_Schlib") (part "ESR10EZPF1000"))
    )
    (comp (ref "R46")
      (value "100Ohm")
      (footprint "FP-ESR10-IPC_A")
      (description "Res Thick Film 0805 100 Ohm 1% 2/5W ±100ppm/°C Molded SMD Paper T/R")
      (fields
        (field (name "MANUFACTURER") "Rohm")
        (field (name "MANUFACTURER PART NUMBER") "ESR10EZPF1000")
        (field (name "SUPPLIER PART NUMBER 1") "755-ESR10EZPF1000")
      )
      (libsource (lib "interface_Schlib") (part "ESR10EZPF1000"))
    )
    (comp (ref "R47")
      (value "100Ohm")
      (footprint "FP-ESR10-IPC_A")
      (description "Res Thick Film 0805 100 Ohm 1% 2/5W ±100ppm/°C Molded SMD Paper T/R")
      (fields
        (field (name "MANUFACTURER") "Rohm")
        (field (name "MANUFACTURER PART NUMBER") "ESR10EZPF1000")
        (field (name "SUPPLIER PART NUMBER 1") "755-ESR10EZPF1000")
      )
      (libsource (lib "interface_Schlib") (part "ESR10EZPF1000"))
    )
    (comp (ref "R51")
      (value "1kOhm")
      (footprint "FP-ESR10-IPC_A")
      (description "Res Thick Film 0805 1K Ohm 1% 0.4W ±100ppm/C Epoxy Resin Pad SMD Automotive T/R")
      (fields
        (field (name "MANUFACTURER") "Rohm")
        (field (name "MANUFACTURER PART NUMBER") "ESR10EZPF1001")
        (field (name "SUPPLIER PART NUMBER 1") "755-ESR10EZPF1001")
      )
      (libsource (lib "interface_Schlib") (part "ESR10EZPF1001"))
    )
    (comp (ref "R52")
      (value "10kOhm")
      (footprint "FP-ESR10-IPC_A")
      (description "Res Thick Film 0805 10K Ohm 1% 0.4W ±100ppm/C Pad SMD Automotive T/R")
      (fields
        (field (name "MANUFACTURER") "Rohm")
        (field (name "MANUFACTURER PART NUMBER") "ESR10EZPF1002")
        (field (name "SUPPLIER PART NUMBER 1") "755-ESR10EZPF1002")
      )
      (libsource (lib "interface_Schlib") (part "ESR10EZPF1002"))
    )
    (comp (ref "R53")
      (value "100kOhm")
      (footprint "FP-ESR10-IPC_A")
      (description "Res Thick Film 0805 100K Ohm 1% 0.4W ±100ppm/C Epoxy Resin Pad SMD Automotive T/R")
      (fields
        (field (name "MANUFACTURER") "Rohm")
        (field (name "MANUFACTURER PART NUMBER") "ESR10EZPF1003")
        (field (name "SUPPLIER PART NUMBER 1") "755-ESR10EZPF1003")
      )
      (libsource (lib "interface_Schlib") (part "ESR10EZPF1003"))
    )
    (comp (ref "R54")
      (value "100Ohm")
      (footprint "FP-ESR10-IPC_A")
      (description "Res Thick Film 0805 100 Ohm 1% 2/5W ±100ppm/°C Molded SMD Paper T/R")
      (fields
        (field (name "MANUFACTURER") "Rohm")
        (field (name "MANUFACTURER PART NUMBER") "ESR10EZPF1000")
        (field (name "SUPPLIER PART NUMBER 1") "755-ESR10EZPF1000")
      )
      (libsource (lib "interface_Schlib") (part "ESR10EZPF1000"))
    )
    (comp (ref "R55")
      (value "1kOhm")
      (footprint "FP-ESR10-IPC_A")
      (description "Res Thick Film 0805 1K Ohm 1% 0.4W ±100ppm/C Epoxy Resin Pad SMD Automotive T/R")
      (fields
        (field (name "MANUFACTURER") "Rohm")
        (field (name "MANUFACTURER PART NUMBER") "ESR10EZPF1001")
        (field (name "SUPPLIER PART NUMBER 1") "755-ESR10EZPF1001")
      )
      (libsource (lib "interface_Schlib") (part "ESR10EZPF1001"))
    )
    (comp (ref "R56")
      (value "1kOhm")
      (footprint "FP-ESR10-IPC_A")
      (description "Res Thick Film 0805 1K Ohm 1% 0.4W ±100ppm/C Epoxy Resin Pad SMD Automotive T/R")
      (fields
        (field (name "MANUFACTURER") "Rohm")
        (field (name "MANUFACTURER PART NUMBER") "ESR10EZPF1001")
        (field (name "SUPPLIER PART NUMBER 1") "755-ESR10EZPF1001")
      )
      (libsource (lib "interface_Schlib") (part "ESR10EZPF1001"))
    )
    (comp (ref "R57")
      (value "820Ohm")
      (footprint "FP-ESR10-IPC_A")
      (description "Res Thick Film 0805 820 Ohm 5% 0.4W ±200ppm/C Epoxy Resin Pad SMD Automotive T/R")
      (fields
        (field (name "MANUFACTURER") "Rohm")
        (field (name "MANUFACTURER PART NUMBER") "ESR10EZPJ821")
        (field (name "SUPPLIER PART NUMBER 1") "755-ESR10EZPJ821")
      )
      (libsource (lib "interface_Schlib") (part "ESR10EZPJ821"))
    )
    (comp (ref "R58")
      (value "1kOhm")
      (footprint "FP-ESR10-IPC_A")
      (description "Res Thick Film 0805 1K Ohm 1% 0.4W ±100ppm/C Epoxy Resin Pad SMD Automotive T/R")
      (fields
        (field (name "MANUFACTURER") "Rohm")
        (field (name "MANUFACTURER PART NUMBER") "ESR10EZPF1001")
        (field (name "SUPPLIER PART NUMBER 1") "755-ESR10EZPF1001")
      )
      (libsource (lib "interface_Schlib") (part "ESR10EZPF1001"))
    )
    (comp (ref "R59")
      (value "10kOhm")
      (footprint "FP-ESR10-IPC_A")
      (description "Res Thick Film 0805 10K Ohm 1% 0.4W ±100ppm/C Pad SMD Automotive T/R")
      (fields
        (field (name "MANUFACTURER") "Rohm")
        (field (name "MANUFACTURER PART NUMBER") "ESR10EZPF1002")
        (field (name "SUPPLIER PART NUMBER 1") "755-ESR10EZPF1002")
      )
      (libsource (lib "interface_Schlib") (part "ESR10EZPF1002"))
    )
    (comp (ref "R61")
      (value "52.3kOhm")
      (footprint "FP-KTR10-IPC_A")
      (description "Res High Voltage 0805 52.3K Ohm 1/8W 1% SMD")
      (fields
        (field (name "MANUFACTURER") "Rohm")
        (field (name "MANUFACTURER PART NUMBER") "KTR10EZPF5232")
        (field (name "SUPPLIER PART NUMBER 1") "755-KTR10EZPF5232")
      )
      (libsource (lib "interface_Schlib") (part "KTR10EZPF5232"))
    )
    (comp (ref "R62")
      (value "10kOhm")
      (footprint "FP-ESR10-IPC_A")
      (description "Res Thick Film 0805 10K Ohm 1% 0.4W ±100ppm/C Pad SMD Automotive T/R")
      (fields
        (field (name "MANUFACTURER") "Rohm")
        (field (name "MANUFACTURER PART NUMBER") "ESR10EZPF1002")
        (field (name "SUPPLIER PART NUMBER 1") "755-ESR10EZPF1002")
      )
      (libsource (lib "interface_Schlib") (part "ESR10EZPF1002"))
    )
    (comp (ref "R510")
      (value "100kOhm")
      (footprint "FP-ESR10-IPC_A")
      (description "Res Thick Film 0805 100K Ohm 1% 0.4W ±100ppm/C Epoxy Resin Pad SMD Automotive T/R")
      (fields
        (field (name "MANUFACTURER") "Rohm")
        (field (name "MANUFACTURER PART NUMBER") "ESR10EZPF1003")
        (field (name "SUPPLIER PART NUMBER 1") "755-ESR10EZPF1003")
      )
      (libsource (lib "interface_Schlib") (part "ESR10EZPF1003"))
    )
    (comp (ref "R511")
      (value "100Ohm")
      (footprint "FP-ESR10-IPC_A")
      (description "Res Thick Film 0805 100 Ohm 1% 2/5W ±100ppm/°C Molded SMD Paper T/R")
      (fields
        (field (name "MANUFACTURER") "Rohm")
        (field (name "MANUFACTURER PART NUMBER") "ESR10EZPF1000")
        (field (name "SUPPLIER PART NUMBER 1") "755-ESR10EZPF1000")
      )
      (libsource (lib "interface_Schlib") (part "ESR10EZPF1000"))
    )
    (comp (ref "R512")
      (value "1kOhm")
      (footprint "FP-ESR10-IPC_A")
      (description "Res Thick Film 0805 1K Ohm 1% 0.4W ±100ppm/C Epoxy Resin Pad SMD Automotive T/R")
      (fields
        (field (name "MANUFACTURER") "Rohm")
        (field (name "MANUFACTURER PART NUMBER") "ESR10EZPF1001")
        (field (name "SUPPLIER PART NUMBER 1") "755-ESR10EZPF1001")
      )
      (libsource (lib "interface_Schlib") (part "ESR10EZPF1001"))
    )
    (comp (ref "R513")
      (value "1kOhm")
      (footprint "FP-ESR10-IPC_A")
      (description "Res Thick Film 0805 1K Ohm 1% 0.4W ±100ppm/C Epoxy Resin Pad SMD Automotive T/R")
      (fields
        (field (name "MANUFACTURER") "Rohm")
        (field (name "MANUFACTURER PART NUMBER") "ESR10EZPF1001")
        (field (name "SUPPLIER PART NUMBER 1") "755-ESR10EZPF1001")
      )
      (libsource (lib "interface_Schlib") (part "ESR10EZPF1001"))
    )
    (comp (ref "R514")
      (value "820Ohm")
      (footprint "FP-ESR10-IPC_A")
      (description "Res Thick Film 0805 820 Ohm 5% 0.4W ±200ppm/C Epoxy Resin Pad SMD Automotive T/R")
      (fields
        (field (name "MANUFACTURER") "Rohm")
        (field (name "MANUFACTURER PART NUMBER") "ESR10EZPJ821")
        (field (name "SUPPLIER PART NUMBER 1") "755-ESR10EZPJ821")
      )
      (libsource (lib "interface_Schlib") (part "ESR10EZPJ821"))
    )
    (comp (ref "R515")
      (value "1kOhm")
      (footprint "FP-ESR10-IPC_A")
      (description "Res Thick Film 0805 1K Ohm 1% 0.4W ±100ppm/C Epoxy Resin Pad SMD Automotive T/R")
      (fields
        (field (name "MANUFACTURER") "Rohm")
        (field (name "MANUFACTURER PART NUMBER") "ESR10EZPF1001")
        (field (name "SUPPLIER PART NUMBER 1") "755-ESR10EZPF1001")
      )
      (libsource (lib "interface_Schlib") (part "ESR10EZPF1001"))
    )
    (comp (ref "R516")
      (value "10kOhm")
      (footprint "FP-ESR10-IPC_A")
      (description "Res Thick Film 0805 10K Ohm 1% 0.4W ±100ppm/C Pad SMD Automotive T/R")
      (fields
        (field (name "MANUFACTURER") "Rohm")
        (field (name "MANUFACTURER PART NUMBER") "ESR10EZPF1002")
        (field (name "SUPPLIER PART NUMBER 1") "755-ESR10EZPF1002")
      )
      (libsource (lib "interface_Schlib") (part "ESR10EZPF1002"))
    )
    (comp (ref "R517")
      (value "100kOhm")
      (footprint "FP-ESR10-IPC_A")
      (description "Res Thick Film 0805 100K Ohm 1% 0.4W ±100ppm/C Epoxy Resin Pad SMD Automotive T/R")
      (fields
        (field (name "MANUFACTURER") "Rohm")
        (field (name "MANUFACTURER PART NUMBER") "ESR10EZPF1003")
        (field (name "SUPPLIER PART NUMBER 1") "755-ESR10EZPF1003")
      )
      (libsource (lib "interface_Schlib") (part "ESR10EZPF1003"))
    )
    (comp (ref "R518")
      (value "100Ohm")
      (footprint "FP-ESR10-IPC_A")
      (description "Res Thick Film 0805 100 Ohm 1% 2/5W ±100ppm/°C Molded SMD Paper T/R")
      (fields
        (field (name "MANUFACTURER") "Rohm")
        (field (name "MANUFACTURER PART NUMBER") "ESR10EZPF1000")
        (field (name "SUPPLIER PART NUMBER 1") "755-ESR10EZPF1000")
      )
      (libsource (lib "interface_Schlib") (part "ESR10EZPF1000"))
    )
    (comp (ref "R519")
      (value "1kOhm")
      (footprint "FP-ESR10-IPC_A")
      (description "Res Thick Film 0805 1K Ohm 1% 0.4W ±100ppm/C Epoxy Resin Pad SMD Automotive T/R")
      (fields
        (field (name "MANUFACTURER") "Rohm")
        (field (name "MANUFACTURER PART NUMBER") "ESR10EZPF1001")
        (field (name "SUPPLIER PART NUMBER 1") "755-ESR10EZPF1001")
      )
      (libsource (lib "interface_Schlib") (part "ESR10EZPF1001"))
    )
    (comp (ref "R520")
      (value "1kOhm")
      (footprint "FP-ESR10-IPC_A")
      (description "Res Thick Film 0805 1K Ohm 1% 0.4W ±100ppm/C Epoxy Resin Pad SMD Automotive T/R")
      (fields
        (field (name "MANUFACTURER") "Rohm")
        (field (name "MANUFACTURER PART NUMBER") "ESR10EZPF1001")
        (field (name "SUPPLIER PART NUMBER 1") "755-ESR10EZPF1001")
      )
      (libsource (lib "interface_Schlib") (part "ESR10EZPF1001"))
    )
    (comp (ref "R521")
      (value "820Ohm")
      (footprint "FP-ESR10-IPC_A")
      (description "Res Thick Film 0805 820 Ohm 5% 0.4W ±200ppm/C Epoxy Resin Pad SMD Automotive T/R")
      (fields
        (field (name "MANUFACTURER") "Rohm")
        (field (name "MANUFACTURER PART NUMBER") "ESR10EZPJ821")
        (field (name "SUPPLIER PART NUMBER 1") "755-ESR10EZPJ821")
      )
      (libsource (lib "interface_Schlib") (part "ESR10EZPJ821"))
    )
    (comp (ref "R522")
      (value "1kOhm")
      (footprint "FP-ESR10-IPC_A")
      (description "Res Thick Film 0805 1K Ohm 1% 0.4W ±100ppm/C Epoxy Resin Pad SMD Automotive T/R")
      (fields
        (field (name "MANUFACTURER") "Rohm")
        (field (name "MANUFACTURER PART NUMBER") "ESR10EZPF1001")
        (field (name "SUPPLIER PART NUMBER 1") "755-ESR10EZPF1001")
      )
      (libsource (lib "interface_Schlib") (part "ESR10EZPF1001"))
    )
    (comp (ref "R523")
      (value "10kOhm")
      (footprint "FP-ESR10-IPC_A")
      (description "Res Thick Film 0805 10K Ohm 1% 0.4W ±100ppm/C Pad SMD Automotive T/R")
      (fields
        (field (name "MANUFACTURER") "Rohm")
        (field (name "MANUFACTURER PART NUMBER") "ESR10EZPF1002")
        (field (name "SUPPLIER PART NUMBER 1") "755-ESR10EZPF1002")
      )
      (libsource (lib "interface_Schlib") (part "ESR10EZPF1002"))
    )
    (comp (ref "R524")
      (value "100kOhm")
      (footprint "FP-ESR10-IPC_A")
      (description "Res Thick Film 0805 100K Ohm 1% 0.4W ±100ppm/C Epoxy Resin Pad SMD Automotive T/R")
      (fields
        (field (name "MANUFACTURER") "Rohm")
        (field (name "MANUFACTURER PART NUMBER") "ESR10EZPF1003")
        (field (name "SUPPLIER PART NUMBER 1") "755-ESR10EZPF1003")
      )
      (libsource (lib "interface_Schlib") (part "ESR10EZPF1003"))
    )
    (comp (ref "R525")
      (value "100Ohm")
      (footprint "FP-ESR10-IPC_A")
      (description "Res Thick Film 0805 100 Ohm 1% 2/5W ±100ppm/°C Molded SMD Paper T/R")
      (fields
        (field (name "MANUFACTURER") "Rohm")
        (field (name "MANUFACTURER PART NUMBER") "ESR10EZPF1000")
        (field (name "SUPPLIER PART NUMBER 1") "755-ESR10EZPF1000")
      )
      (libsource (lib "interface_Schlib") (part "ESR10EZPF1000"))
    )
    (comp (ref "R526")
      (value "1kOhm")
      (footprint "FP-ESR10-IPC_A")
      (description "Res Thick Film 0805 1K Ohm 1% 0.4W ±100ppm/C Epoxy Resin Pad SMD Automotive T/R")
      (fields
        (field (name "MANUFACTURER") "Rohm")
        (field (name "MANUFACTURER PART NUMBER") "ESR10EZPF1001")
        (field (name "SUPPLIER PART NUMBER 1") "755-ESR10EZPF1001")
      )
      (libsource (lib "interface_Schlib") (part "ESR10EZPF1001"))
    )
    (comp (ref "R527")
      (value "1kOhm")
      (footprint "FP-ESR10-IPC_A")
      (description "Res Thick Film 0805 1K Ohm 1% 0.4W ±100ppm/C Epoxy Resin Pad SMD Automotive T/R")
      (fields
        (field (name "MANUFACTURER") "Rohm")
        (field (name "MANUFACTURER PART NUMBER") "ESR10EZPF1001")
        (field (name "SUPPLIER PART NUMBER 1") "755-ESR10EZPF1001")
      )
      (libsource (lib "interface_Schlib") (part "ESR10EZPF1001"))
    )
    (comp (ref "R528")
      (value "820Ohm")
      (footprint "FP-ESR10-IPC_A")
      (description "Res Thick Film 0805 820 Ohm 5% 0.4W ±200ppm/C Epoxy Resin Pad SMD Automotive T/R")
      (fields
        (field (name "MANUFACTURER") "Rohm")
        (field (name "MANUFACTURER PART NUMBER") "ESR10EZPJ821")
        (field (name "SUPPLIER PART NUMBER 1") "755-ESR10EZPJ821")
      )
      (libsource (lib "interface_Schlib") (part "ESR10EZPJ821"))
    )
    (comp (ref "U21")
      (value "TMUX1308PWR")
      (footprint "FP-PW0016A-IPC_A")
      (description "1-CHANNEL, 8:1 GENERAL-PURPOSE A")
      (fields (field (name "SUPPLIER PART NUMBER 1") "595-TMUX1308PWR"))
      (libsource (lib "interface_Schlib") (part "TMUX1308PWR"))
    )
    (comp (ref "U22")
      (value "TMUX1308PWR")
      (footprint "FP-PW0016A-IPC_A")
      (description "1-CHANNEL, 8:1 GENERAL-PURPOSE A")
      (fields (field (name "SUPPLIER PART NUMBER 1") "595-TMUX1308PWR"))
      (libsource (lib "interface_Schlib") (part "TMUX1308PWR"))
    )
    (comp (ref "U23")
      (value "SN74LV1T02DBVRG4")
      (footprint "FP-DBV0005A-IPC_A")
      (description "Single Power Supply 2-input POSITIVE NOR GATE Logic Level Shifter 5-SOT-23 -40 to 125")
      (fields
        (field (name "MANUFACTURER") "Texas Instruments")
        (field (name "SUPPLIER PART NUMBER 1") "595-SN74LV1T02DBVRG4")
      )
      (libsource (lib "") (part "SN74LV1T02DBVRG4_1"))
    )
    (comp (ref "U24")
      (value "SN74LV1T02DBVRG4")
      (footprint "FP-DBV0005A-IPC_A")
      (description "Single Power Supply 2-input POSITIVE NOR GATE Logic Level Shifter 5-SOT-23 -40 to 125")
      (fields
        (field (name "MANUFACTURER") "Texas Instruments")
        (field (name "SUPPLIER PART NUMBER 1") "595-SN74LV1T02DBVRG4")
      )
      (libsource (lib "interface_Schlib") (part "SN74LV1T02DBVRG4"))
    )
    (comp (ref "U31")
      (value "ADC101C021CIMKX/NOPB")
      (footprint "MK06A_N")
      (description "10-Bit, 189kSPS, 1-Ch SAR ADC with I2C and Alert Pin 6-SOT-23-THIN -40 to 105")
      (fields
        (field (name "MANUFACTURER") "TI National Semiconductor")
        (field (name "SUPPLIER PART NUMBER 1") "926-A101C021CIMKXNPB")
      )
      (libsource (lib "interface_Schlib") (part "ADC101C021CIMKX/NOPB"))
    )
    (comp (ref "U61")
      (value "AP62301WU-7")
      (footprint "TSOP95P280X100-6N")
      (description "Converter DC to DC 4.2V to 18V Synchronous Step Down Single-Out 3A 6-Pin TSOT-26 T/R")
      (fields
        (field (name "MANUFACTURER") "Diodes")
        (field (name "SUPPLIER PART NUMBER 1") "621-AP62301WU-7")
      )
      (libsource (lib "interface_Schlib") (part "AP62301WU-7"))
    )
  )
  (nets
    (net (code "1") (name "+3V3") (class "Default")
      (node (ref "C32") (pin "2") (pinfunction "2_2") (pintype "passive"))
      (node (ref "C33") (pin "2") (pinfunction "2_2") (pintype "passive"))
      (node (ref "C34") (pin "2") (pinfunction "2_2") (pintype "passive"))
      (node (ref "C510") (pin "2") (pinfunction "2_2") (pintype "passive"))
      (node (ref "C54") (pin "2") (pinfunction "2_2") (pintype "passive"))
      (node (ref "J12") (pin "17") (pinfunction "17_17") (pintype "passive"))
      (node (ref "J12") (pin "19") (pinfunction "19_19") (pintype "passive"))
      (node (ref "J12") (pin "5") (pinfunction "5_5") (pintype "passive"))
      (node (ref "J12") (pin "7") (pinfunction "7_7") (pintype "passive"))
      (node (ref "J12") (pin "9") (pinfunction "9_9") (pintype "passive"))
      (node (ref "J13") (pin "3") (pinfunction "3_3") (pintype "passive"))
      (node (ref "J32") (pin "2") (pinfunction "2_2") (pintype "passive"))
      (node (ref "J33") (pin "1") (pinfunction "1_1") (pintype "passive"))
      (node (ref "J52") (pin "1") (pinfunction "1_1") (pintype "passive"))
      (node (ref "J54") (pin "1") (pinfunction "1_1") (pintype "passive"))
      (node (ref "Q54") (pin "3") (pinfunction "3_3") (pintype "passive"))
      (node (ref "Q56") (pin "3") (pinfunction "3_3") (pintype "passive"))
      (node (ref "R33") (pin "1") (pinfunction "1_1") (pintype "passive"))
      (node (ref "R510") (pin "2") (pinfunction "2_2") (pintype "passive"))
      (node (ref "R517") (pin "2") (pinfunction "2_2") (pintype "passive"))
      (node (ref "R524") (pin "2") (pinfunction "2_2") (pintype "passive"))
      (node (ref "R53") (pin "2") (pinfunction "2_2") (pintype "passive"))
      (node (ref "U31") (pin "1") (pinfunction "VA_1") (pintype "power_in"))
    )
    (net (code "2") (name "+3V3_NFC") (class "Default")
      (node (ref "C511") (pin "2") (pinfunction "2_2") (pintype "passive"))
      (node (ref "J31") (pin "1") (pinfunction "1_1") (pintype "passive"))
      (node (ref "J54") (pin "2") (pinfunction "2_2") (pintype "passive"))
      (node (ref "Q56") (pin "2") (pinfunction "2_2") (pintype "passive"))
    )
    (net (code "3") (name "+3V3_US") (class "Default")
      (node (ref "C24") (pin "2") (pinfunction "2_2") (pintype "passive"))
      (node (ref "C55") (pin "2") (pinfunction "2_2") (pintype "passive"))
      (node (ref "J52") (pin "2") (pinfunction "2_2") (pintype "passive"))
      (node (ref "Q54") (pin "2") (pinfunction "2_2") (pintype "passive"))
      (node (ref "U24") (pin "5") (pinfunction "VCC_5") (pintype "passive"))
    )
    (net (code "4") (name "+5V") (class "Default")
      (node (ref "C51") (pin "2") (pinfunction "2_2") (pintype "passive"))
      (node (ref "C57") (pin "2") (pinfunction "2_2") (pintype "passive"))
      (node (ref "J12") (pin "2") (pinfunction "2_2") (pintype "passive"))
      (node (ref "J12") (pin "4") (pinfunction "4_4") (pintype "passive"))
      (node (ref "J12") (pin "6") (pinfunction "6_6") (pintype "passive"))
      (node (ref "J51") (pin "1") (pinfunction "1_1") (pintype "passive"))
      (node (ref "J53") (pin "1") (pinfunction "1_1") (pintype "passive"))
      (node (ref "Q53") (pin "3") (pinfunction "3_3") (pintype "passive"))
      (node (ref "Q55") (pin "3") (pinfunction "3_3") (pintype "passive"))
      (node (ref "R41") (pin "2") (pinfunction "2_2") (pintype "passive"))
      (node (ref "R42") (pin "2") (pinfunction "2_2") (pintype "passive"))
      (node (ref "R43") (pin "2") (pinfunction "2_2") (pintype "passive"))
    )
    (net (code "5") (name "+5V_GSM") (class "Default")
      (node (ref "C11") (pin "2") (pinfunction "2_2") (pintype "passive"))
      (node (ref "C12") (pin "2") (pinfunction "2_2") (pintype "passive"))
      (node (ref "C13") (pin "2") (pinfunction "2_2") (pintype "passive"))
      (node (ref "C58") (pin "2") (pinfunction "2_2") (pintype "passive"))
      (node (ref "J13") (pin "1") (pinfunction "1_1") (pintype "passive"))
      (node (ref "J53") (pin "2") (pinfunction "2_2") (pintype "passive"))
      (node (ref "Q55") (pin "2") (pinfunction "2_2") (pintype "passive"))
    )
    (net (code "6") (name "+5V_US") (class "Default")
      (node (ref "C21") (pin "2") (pinfunction "2_2") (pintype "passive"))
      (node (ref "C22") (pin "2") (pinfunction "2_2") (pintype "passive"))
      (node (ref "C23") (pin "2") (pinfunction "2_2") (pintype "passive"))
      (node (ref "C52") (pin "2") (pinfunction "2_2") (pintype "passive"))
      (node (ref "J21") (pin "1") (pinfunction "1_1") (pintype "passive"))
      (node (ref "J22") (pin "1") (pinfunction "1_1") (pintype "passive"))
      (node (ref "J23") (pin "1") (pinfunction "1_1") (pintype "passive"))
      (node (ref "J24") (pin "1") (pinfunction "1_1") (pintype "passive"))
      (node (ref "J25") (pin "1") (pinfunction "1_1") (pintype "passive"))
      (node (ref "J51") (pin "2") (pinfunction "2_2") (pintype "passive"))
      (node (ref "Q53") (pin "2") (pinfunction "2_2") (pintype "passive"))
      (node (ref "U21") (pin "16") (pinfunction "VDD_16") (pintype "power_in"))
      (node (ref "U22") (pin "16") (pinfunction "VDD_16") (pintype "power_in"))
      (node (ref "U23") (pin "5") (pinfunction "VCC_5") (pintype "passive"))
    )
    (net (code "7") (name "+5V_ZYBO") (class "Default")
      (node (ref "C621") (pin "2") (pinfunction "2_2") (pintype "passive"))
      (node (ref "C622") (pin "2") (pinfunction "2_2") (pintype "passive"))
      (node (ref "J01") (pin "1") (pinfunction "1_1") (pintype "passive"))
      (node (ref "L61") (pin "2") (pinfunction "2_2") (pintype "passive"))
      (node (ref "R44") (pin "2") (pinfunction "2_2") (pintype "passive"))
      (node (ref "R61") (pin "2") (pinfunction "2_2") (pintype "passive"))
    )
    (net (code "8") (name "+12V") (class "Default")
      (node (ref "C61") (pin "2") (pinfunction "2_2") (pintype "passive"))
      (node (ref "J12") (pin "14") (pinfunction "14_14") (pintype "passive"))
      (node (ref "J12") (pin "16") (pinfunction "16_16") (pintype "passive"))
      (node (ref "J12") (pin "18") (pinfunction "18_18") (pintype "passive"))
      (node (ref "R31") (pin "2") (pinfunction "2_2") (pintype "passive"))
      (node (ref "R516") (pin "1") (pinfunction "1_1") (pintype "passive"))
      (node (ref "R52") (pin "1") (pinfunction "1_1") (pintype "passive"))
      (node (ref "R523") (pin "1") (pinfunction "1_1") (pintype "passive"))
      (node (ref "R59") (pin "1") (pinfunction "1_1") (pintype "passive"))
      (node (ref "U61") (pin "3") (pinfunction "3_3") (pintype "passive"))
    )
    (net (code "9") (name "/BALISE_I2C_SCL") (class "Default")
      (node (ref "J33") (pin "4") (pinfunction "4_4") (pintype "passive"))
      (node (ref "J34") (pin "2") (pinfunction "2_2") (pintype "passive"))
    )
    (net (code "10") (name "/BALISE_I2C_SDA") (class "Default")
      (node (ref "J33") (pin "3") (pinfunction "3_3") (pintype "passive"))
      (node (ref "J34") (pin "9") (pinfunction "9_9") (pintype "passive"))
    )
    (net (code "11") (name "/BAT_ALERT") (class "Default")
      (node (ref "J14") (pin "1") (pinfunction "1_1") (pintype "passive"))
      (node (ref "R33") (pin "2") (pinfunction "2_2") (pintype "passive"))
      (node (ref "R47") (pin "1") (pinfunction "1_1") (pintype "passive"))
      (node (ref "U31") (pin "4") (pinfunction "ALERT_4") (pintype "open_collector"))
    )
    (net (code "12") (name "/BAT_I2C_SCL") (class "Default")
      (node (ref "J14") (pin "3") (pinfunction "3_3") (pintype "passive"))
      (node (ref "U31") (pin "5") (pinfunction "SCL_5") (pintype "input"))
    )
    (net (code "13") (name "/BAT_I2C_SDA") (class "Default")
      (node (ref "J14") (pin "9") (pinfunction "9_9") (pintype "passive"))
      (node (ref "U31") (pin "6") (pinfunction "SDA_6") (pintype "bidirectional"))
    )
    (net (code "14") (name "/GSM_RST") (class "Default")
      (node (ref "J13") (pin "7") (pinfunction "7_7") (pintype "passive"))
      (node (ref "J14") (pin "8") (pinfunction "8_8") (pintype "passive"))
    )
    (net (code "15") (name "/GSM_UART_RXD") (class "Default")
      (node (ref "J13") (pin "5") (pinfunction "5_5") (pintype "passive"))
      (node (ref "J14") (pin "2") (pinfunction "2_2") (pintype "passive"))
    )
    (net (code "16") (name "/GSM_UART_TXD") (class "Default")
      (node (ref "J13") (pin "4") (pinfunction "4_4") (pintype "passive"))
      (node (ref "J14") (pin "7") (pinfunction "7_7") (pintype "passive"))
    )
    (net (code "17") (name "/HOLO_LED_DEBUG") (class "Default")
      (node (ref "J11") (pin "16") (pinfunction "16_16") (pintype "passive"))
      (node (ref "R46") (pin "1") (pinfunction "1_1") (pintype "passive"))
    )
    (net (code "18") (name "/HOLO_LED_PWR") (class "Default")
      (node (ref "J11") (pin "14") (pinfunction "14_14") (pintype "passive"))
      (node (ref "R45") (pin "1") (pinfunction "1_1") (pintype "passive"))
    )
    (net (code "19") (name "/HOLO_UART_RX") (class "Default")
      (node (ref "J11") (pin "1") (pinfunction "1_1") (pintype "passive"))
      (node (ref "J14") (pin "4") (pinfunction "4_4") (pintype "passive"))
    )
    (net (code "20") (name "/HOLO_UART_TX") (class "Default")
      (node (ref "J11") (pin "3") (pinfunction "3_3") (pintype "passive"))
      (node (ref "J14") (pin "10") (pinfunction "10_10") (pintype "passive"))
    )
    (net (code "21") (name "/IMU_I2C_SCL") (class "Default")
      (node (ref "J32") (pin "4") (pinfunction "4_4") (pintype "passive"))
      (node (ref "J34") (pin "3") (pinfunction "3_3") (pintype "passive"))
    )
    (net (code "22") (name "/IMU_I2C_SDA") (class "Default")
      (node (ref "J32") (pin "3") (pinfunction "3_3") (pintype "passive"))
      (node (ref "J34") (pin "4") (pinfunction "4_4") (pintype "passive"))
    )
    (net (code "23") (name "/NFC_FD") (class "Default")
      (node (ref "J31") (pin "3") (pinfunction "3_3") (pintype "passive"))
      (node (ref "J34") (pin "8") (pinfunction "8_8") (pintype "passive"))
    )
    (net (code "24") (name "/NFC_I2C_SCL") (class "Default")
      (node (ref "J31") (pin "5") (pinfunction "5_5") (pintype "passive"))
      (node (ref "J34") (pin "7") (pinfunction "7_7") (pintype "passive"))
    )
    (net (code "25") (name "/NFC_I2C_SDA") (class "Default")
      (node (ref "J31") (pin "4") (pinfunction "4_4") (pintype "passive"))
      (node (ref "J34") (pin "1") (pinfunction "1_1") (pintype "passive"))
    )
    (net (code "26") (name "/PWR_MGT_GSM") (class "Default")
      (node (ref "J26") (pin "4") (pinfunction "4_4") (pintype "passive"))
      (node (ref "R518") (pin "1") (pinfunction "1_1") (pintype "passive"))
    )
    (net (code "27") (name "/PWR_MGT_NFC") (class "Default")
      (node (ref "J26") (pin "10") (pinfunction "10_10") (pintype "passive"))
      (node (ref "R525") (pin "1") (pinfunction "1_1") (pintype "passive"))
    )
    (net (code "28") (name "/PWR_MGT_US") (class "Default")
      (node (ref "J26") (pin "9") (pinfunction "9_9") (pintype "passive"))
      (node (ref "R511") (pin "1") (pinfunction "1_1") (pintype "passive"))
      (node (ref "R54") (pin "1") (pinfunction "1_1") (pintype "passive"))
    )
    (net (code "29") (name "/US_1_ECHO_5V") (class "Default")
      (node (ref "J21") (pin "3") (pinfunction "3_3") (pintype "passive"))
      (node (ref "U22") (pin "12") (pinfunction "S3_12") (pintype "bidirectional"))
    )
    (net (code "30") (name "/US_1_TRIG_5V") (class "Default")
      (node (ref "J21") (pin "2") (pinfunction "2_2") (pintype "passive"))
      (node (ref "U21") (pin "12") (pinfunction "S3_12") (pintype "bidirectional"))
    )
    (net (code "31") (name "/US_2_ECHO_5V") (class "Default")
      (node (ref "J22") (pin "3") (pinfunction "3_3") (pintype "passive"))
      (node (ref "U22") (pin "13") (pinfunction "S0_13") (pintype "bidirectional"))
    )
    (net (code "32") (name "/US_2_TRIG_5V") (class "Default")
      (node (ref "J22") (pin "2") (pinfunction "2_2") (pintype "passive"))
      (node (ref "U21") (pin "13") (pinfunction "S0_13") (pintype "bidirectional"))
    )
    (net (code "33") (name "/US_3_ECHO_5V") (class "Default")
      (node (ref "J23") (pin "3") (pinfunction "3_3") (pintype "passive"))
      (node (ref "U22") (pin "14") (pinfunction "S1_14") (pintype "bidirectional"))
    )
    (net (code "34") (name "/US_3_TRIG_5V") (class "Default")
      (node (ref "J23") (pin "2") (pinfunction "2_2") (pintype "passive"))
      (node (ref "U21") (pin "14") (pinfunction "S1_14") (pintype "bidirectional"))
    )
    (net (code "35") (name "/US_4_ECHO_5V") (class "Default")
      (node (ref "J24") (pin "3") (pinfunction "3_3") (pintype "passive"))
      (node (ref "U22") (pin "15") (pinfunction "S2_15") (pintype "bidirectional"))
    )
    (net (code "36") (name "/US_4_TRIG_5V") (class "Default")
      (node (ref "J24") (pin "2") (pinfunction "2_2") (pintype "passive"))
      (node (ref "U21") (pin "15") (pinfunction "S2_15") (pintype "bidirectional"))
    )
    (net (code "37") (name "/US_5_ECHO_5V") (class "Default")
      (node (ref "J25") (pin "3") (pinfunction "3_3") (pintype "passive"))
      (node (ref "U22") (pin "1") (pinfunction "S4_1") (pintype "bidirectional"))
    )
    (net (code "38") (name "/US_5_TRIG_5V") (class "Default")
      (node (ref "J25") (pin "2") (pinfunction "2_2") (pintype "passive"))
      (node (ref "U21") (pin "1") (pinfunction "S4_1") (pintype "bidirectional"))
    )
    (net (code "39") (name "/US_ECHO_3V3") (class "Default")
      (node (ref "J26") (pin "8") (pinfunction "8_8") (pintype "passive"))
      (node (ref "R25") (pin "2") (pinfunction "2_2") (pintype "passive"))
    )
    (net (code "40") (name "/US_ECHO_5V") (class "Default")
      (node (ref "U22") (pin "3") (pinfunction "D_3") (pintype "bidirectional"))
      (node (ref "U24") (pin "1") (pinfunction "1_1") (pintype "passive"))
      (node (ref "U24") (pin "2") (pinfunction "2_2") (pintype "passive"))
    )
    (net (code "41") (name "/US_SEL_0") (class "Default")
      (node (ref "J26") (pin "1") (pinfunction "1_1") (pintype "passive"))
      (node (ref "R21") (pin "2") (pinfunction "2_2") (pintype "passive"))
    )
    (net (code "42") (name "/US_SEL_1") (class "Default")
      (node (ref "J26") (pin "2") (pinfunction "2_2") (pintype "passive"))
      (node (ref "R22") (pin "2") (pinfunction "2_2") (pintype "passive"))
    )
    (net (code "43") (name "/US_SEL_2") (class "Default")
      (node (ref "J26") (pin "3") (pinfunction "3_3") (pintype "passive"))
      (node (ref "R23") (pin "2") (pinfunction "2_2") (pintype "passive"))
    )
    (net (code "44") (name "/US_TRIG_3V3") (class "Default")
      (node (ref "J26") (pin "7") (pinfunction "7_7") (pintype "passive"))
      (node (ref "R24") (pin "1") (pinfunction "1_1") (pintype "passive"))
    )
    (net (code "45") (name "/US_TRIG_5V") (class "Default")
      (node (ref "U21") (pin "3") (pinfunction "D_3") (pintype "bidirectional"))
      (node (ref "U23") (pin "4") (pinfunction "4_4") (pintype "passive"))
    )
    (net (code "46") (name "GND") (class "Default")
      (node (ref "C11") (pin "1") (pinfunction "1_1") (pintype "passive"))
      (node (ref "C12") (pin "1") (pinfunction "1_1") (pintype "passive"))
      (node (ref "C13") (pin "1") (pinfunction "1_1") (pintype "passive"))
      (node (ref "C21") (pin "1") (pinfunction "1_1") (pintype "passive"))
      (node (ref "C22") (pin "1") (pinfunction "1_1") (pintype "passive"))
      (node (ref "C23") (pin "1") (pinfunction "1_1") (pintype "passive"))
      (node (ref "C24") (pin "1") (pinfunction "1_1") (pintype "passive"))
      (node (ref "C31") (pin "1") (pinfunction "1_1") (pintype "passive"))
      (node (ref "C32") (pin "1") (pinfunction "1_1") (pintype "passive"))
      (node (ref "C33") (pin "1") (pinfunction "1_1") (pintype "passive"))
      (node (ref "C34") (pin "1") (pinfunction "1_1") (pintype "passive"))
      (node (ref "C512") (pin "1") (pinfunction "1_1") (pintype "passive"))
      (node (ref "C53") (pin "1") (pinfunction "1_1") (pintype "passive"))
      (node (ref "C56") (pin "1") (pinfunction "1_1") (pintype "passive"))
      (node (ref "C59") (pin "1") (pinfunction "1_1") (pintype "passive"))
      (node (ref "C61") (pin "1") (pinfunction "1_1") (pintype "passive"))
      (node (ref "C621") (pin "1") (pinfunction "1_1") (pintype "passive"))
      (node (ref "C622") (pin "1") (pinfunction "1_1") (pintype "passive"))
      (node (ref "D4") (pin "1") (pinfunction "1_1") (pintype "passive"))
      (node (ref "J01") (pin "2") (pinfunction "2_2") (pintype "passive"))
      (node (ref "J01") (pin "3") (pinfunction "3_3") (pintype "passive"))
      (node (ref "J11") (pin "10") (pinfunction "10_10") (pintype "passive"))
      (node (ref "J11") (pin "12") (pinfunction "12_12") (pintype "passive"))
      (node (ref "J11") (pin "13") (pinfunction "13_13") (pintype "passive"))
      (node (ref "J11") (pin "15") (pinfunction "15_15") (pintype "passive"))
      (node (ref "J11") (pin "18") (pinfunction "18_18") (pintype "passive"))
      (node (ref "J11") (pin "20") (pinfunction "20_20") (pintype "passive"))
      (node (ref "J11") (pin "5") (pinfunction "5_5") (pintype "passive"))
      (node (ref "J11") (pin "7") (pinfunction "7_7") (pintype "passive"))
      (node (ref "J12") (pin "1") (pinfunction "1_1") (pintype "passive"))
      (node (ref "J12") (pin "10") (pinfunction "10_10") (pintype "passive"))
      (node (ref "J12") (pin "11") (pinfunction "11_11") (pintype "passive"))
      (node (ref "J12") (pin "12") (pinfunction "12_12") (pintype "passive"))
      (node (ref "J12") (pin "13") (pinfunction "13_13") (pintype "passive"))
      (node (ref "J12") (pin "15") (pinfunction "15_15") (pintype "passive"))
      (node (ref "J12") (pin "20") (pinfunction "20_20") (pintype "passive"))
      (node (ref "J12") (pin "3") (pinfunction "3_3") (pintype "passive"))
      (node (ref "J12") (pin "8") (pinfunction "8_8") (pintype "passive"))
      (node (ref "J13") (pin "2") (pinfunction "2_2") (pintype "passive"))
      (node (ref "J13") (pin "6") (pinfunction "6_6") (pintype "passive"))
      (node (ref "J14") (pin "11") (pinfunction "11_11") (pintype "passive"))
      (node (ref "J14") (pin "5") (pinfunction "5_5") (pintype "passive"))
      (node (ref "J21") (pin "4") (pinfunction "4_4") (pintype "passive"))
      (node (ref "J22") (pin "4") (pinfunction "4_4") (pintype "passive"))
      (node (ref "J23") (pin "4") (pinfunction "4_4") (pintype "passive"))
      (node (ref "J24") (pin "4") (pinfunction "4_4") (pintype "passive"))
      (node (ref "J25") (pin "4") (pinfunction "4_4") (pintype "passive"))
      (node (ref "J26") (pin "11") (pinfunction "11_11") (pintype "passive"))
      (node (ref "J26") (pin "5") (pinfunction "5_5") (pintype "passive"))
      (node (ref "J31") (pin "2") (pinfunction "2_2") (pintype "passive"))
      (node (ref "J31") (pin "6") (pinfunction "6_6") (pintype "passive"))
      (node (ref "J32") (pin "1") (pinfunction "1_1") (pintype "passive"))
      (node (ref "J33") (pin "2") (pinfunction "2_2") (pintype "passive"))
      (node (ref "J34") (pin "11") (pinfunction "11_11") (pintype "passive"))
      (node (ref "J34") (pin "5") (pinfunction "5_5") (pintype "passive"))
      (node (ref "Q41") (pin "2") (pinfunction "2_2") (pintype "passive"))
      (node (ref "Q42") (pin "2") (pinfunction "2_2") (pintype "passive"))
      (node (ref "Q43") (pin "2") (pinfunction "2_2") (pintype "passive"))
      (node (ref "R32") (pin "1") (pinfunction "1_1") (pintype "passive"))
      (node (ref "R513") (pin "1") (pinfunction "1_1") (pintype "passive"))
      (node (ref "R514") (pin "1") (pinfunction "1_1") (pintype "passive"))
      (node (ref "R520") (pin "1") (pinfunction "1_1") (pintype "passive"))
      (node (ref "R521") (pin "1") (pinfunction "1_1") (pintype "passive"))
      (node (ref "R527") (pin "1") (pinfunction "1_1") (pintype "passive"))
      (node (ref "R528") (pin "1") (pinfunction "1_1") (pintype "passive"))
      (node (ref "R56") (pin "1") (pinfunction "1_1") (pintype "passive"))
      (node (ref "R57") (pin "1") (pinfunction "1_1") (pintype "passive"))
      (node (ref "R62") (pin "1") (pinfunction "1_1") (pintype "passive"))
      (node (ref "U21") (pin "6") (pinfunction "~{EN}_6") (pintype "input"))
      (node (ref "U21") (pin "8") (pinfunction "GND_8") (pintype "power_in"))
      (node (ref "U22") (pin "6") (pinfunction "~{EN}_6") (pintype "input"))
      (node (ref "U22") (pin "8") (pinfunction "GND_8") (pintype "power_in"))
      (node (ref "U23") (pin "3") (pinfunction "GND_3") (pintype "passive"))
      (node (ref "U24") (pin "3") (pinfunction "GND_3") (pintype "passive"))
      (node (ref "U31") (pin "2") (pinfunction "GND_2") (pintype "power_in"))
      (node (ref "U61") (pin "1") (pinfunction "1_1") (pintype "passive"))
    )
    (net (code "47") (name "Net-(C63-Pad1)") (class "Default")
      (node (ref "C63") (pin "1") (pinfunction "1_1") (pintype "passive"))
      (node (ref "U61") (pin "4") (pinfunction "4_4") (pintype "passive"))
    )
    (net (code "48") (name "Net-(C63-Pad2)") (class "Default")
      (node (ref "C63") (pin "2") (pinfunction "2_2") (pintype "passive"))
      (node (ref "L61") (pin "1") (pinfunction "1_1") (pintype "passive"))
      (node (ref "U61") (pin "2") (pinfunction "2_2") (pintype "passive"))
    )
    (net (code "49") (name "Net-(D1-Pad1)") (class "Default")
      (node (ref "D1") (pin "1") (pinfunction "1_1") (pintype "passive"))
      (node (ref "Q41") (pin "3") (pinfunction "3_3") (pintype "passive"))
    )
    (net (code "50") (name "Net-(D1-Pad2)") (class "Default")
      (node (ref "D1") (pin "2") (pinfunction "2_2") (pintype "passive"))
      (node (ref "R41") (pin "1") (pinfunction "1_1") (pintype "passive"))
    )
    (net (code "51") (name "Net-(D2-Pad1)") (class "Default")
      (node (ref "D2") (pin "1") (pinfunction "1_1") (pintype "passive"))
      (node (ref "Q42") (pin "3") (pinfunction "3_3") (pintype "passive"))
    )
    (net (code "52") (name "Net-(D2-Pad2)") (class "Default")
      (node (ref "D2") (pin "2") (pinfunction "2_2") (pintype "passive"))
      (node (ref "R42") (pin "1") (pinfunction "1_1") (pintype "passive"))
    )
    (net (code "53") (name "Net-(D3-Pad1)") (class "Default")
      (node (ref "D3") (pin "1") (pinfunction "1_1") (pintype "passive"))
      (node (ref "Q43") (pin "3") (pinfunction "3_3") (pintype "passive"))
    )
    (net (code "54") (name "Net-(D3-Pad2)") (class "Default")
      (node (ref "D3") (pin "2") (pinfunction "2_2") (pintype "passive"))
      (node (ref "R43") (pin "1") (pinfunction "1_1") (pintype "passive"))
    )
    (net (code "55") (name "Net-(D4-Pad2)") (class "Default")
      (node (ref "D4") (pin "2") (pinfunction "2_2") (pintype "passive"))
      (node (ref "R44") (pin "1") (pinfunction "1_1") (pintype "passive"))
    )
    (net (code "56") (name "Net-(Q41-Pad1)") (class "Default")
      (node (ref "Q41") (pin "1") (pinfunction "1_1") (pintype "passive"))
      (node (ref "R45") (pin "2") (pinfunction "2_2") (pintype "passive"))
    )
    (net (code "57") (name "Net-(Q42-Pad1)") (class "Default")
      (node (ref "Q42") (pin "1") (pinfunction "1_1") (pintype "passive"))
      (node (ref "R46") (pin "2") (pinfunction "2_2") (pintype "passive"))
    )
    (net (code "58") (name "Net-(Q43-Pad1)") (class "Default")
      (node (ref "Q43") (pin "1") (pinfunction "1_1") (pintype "passive"))
      (node (ref "R47") (pin "2") (pinfunction "2_2") (pintype "passive"))
    )
    (net (code "59") (name "Net-(Q51A-B)") (class "Default")
      (node (ref "C53") (pin "2") (pinfunction "2_2") (pintype "passive"))
      (node (ref "Q51") (pin "2") (pinfunction "B_2") (pintype "passive"))
      (node (ref "R55") (pin "2") (pinfunction "2_2") (pintype "passive"))
      (node (ref "R56") (pin "2") (pinfunction "2_2") (pintype "passive"))
    )
    (net (code "60") (name "Net-(Q51A-C)") (class "Default")
      (node (ref "C51") (pin "1") (pinfunction "1_1") (pintype "passive"))
      (node (ref "C52") (pin "1") (pinfunction "1_1") (pintype "passive"))
      (node (ref "Q51") (pin "6") (pinfunction "C_6") (pintype "passive"))
      (node (ref "R51") (pin "1") (pinfunction "1_1") (pintype "passive"))
      (node (ref "R52") (pin "2") (pinfunction "2_2") (pintype "passive"))
    )
    (net (code "61") (name "Net-(Q51A-E)") (class "Default")
      (node (ref "Q51") (pin "1") (pinfunction "E_1") (pintype "passive"))
      (node (ref "R57") (pin "2") (pinfunction "2_2") (pintype "passive"))
    )
    (net (code "62") (name "Net-(Q51B-B)") (class "Default")
      (node (ref "C59") (pin "2") (pinfunction "2_2") (pintype "passive"))
      (node (ref "Q51") (pin "5") (pinfunction "B_5") (pintype "passive"))
      (node (ref "R519") (pin "2") (pinfunction "2_2") (pintype "passive"))
      (node (ref "R520") (pin "2") (pinfunction "2_2") (pintype "passive"))
    )
    (net (code "63") (name "Net-(Q51B-C)") (class "Default")
      (node (ref "C57") (pin "1") (pinfunction "1_1") (pintype "passive"))
      (node (ref "C58") (pin "1") (pinfunction "1_1") (pintype "passive"))
      (node (ref "Q51") (pin "3") (pinfunction "C_3") (pintype "passive"))
      (node (ref "R515") (pin "1") (pinfunction "1_1") (pintype "passive"))
      (node (ref "R516") (pin "2") (pinfunction "2_2") (pintype "passive"))
    )
    (net (code "64") (name "Net-(Q51B-E)") (class "Default")
      (node (ref "Q51") (pin "4") (pinfunction "E_4") (pintype "passive"))
      (node (ref "R521") (pin "2") (pinfunction "2_2") (pintype "passive"))
    )
    (net (code "65") (name "Net-(Q52A-B)") (class "Default")
      (node (ref "C56") (pin "2") (pinfunction "2_2") (pintype "passive"))
      (node (ref "Q52") (pin "2") (pinfunction "B_2") (pintype "passive"))
      (node (ref "R512") (pin "2") (pinfunction "2_2") (pintype "passive"))
      (node (ref "R513") (pin "2") (pinfunction "2_2") (pintype "passive"))
    )
    (net (code "66") (name "Net-(Q52A-C)") (class "Default")
      (node (ref "C54") (pin "1") (pinfunction "1_1") (pintype "passive"))
      (node (ref "C55") (pin "1") (pinfunction "1_1") (pintype "passive"))
      (node (ref "Q52") (pin "6") (pinfunction "C_6") (pintype "passive"))
      (node (ref "R58") (pin "1") (pinfunction "1_1") (pintype "passive"))
      (node (ref "R59") (pin "2") (pinfunction "2_2") (pintype "passive"))
    )
    (net (code "67") (name "Net-(Q52A-E)") (class "Default")
      (node (ref "Q52") (pin "1") (pinfunction "E_1") (pintype "passive"))
      (node (ref "R514") (pin "2") (pinfunction "2_2") (pintype "passive"))
    )
    (net (code "68") (name "Net-(Q52B-B)") (class "Default")
      (node (ref "C512") (pin "2") (pinfunction "2_2") (pintype "passive"))
      (node (ref "Q52") (pin "5") (pinfunction "B_5") (pintype "passive"))
      (node (ref "R526") (pin "2") (pinfunction "2_2") (pintype "passive"))
      (node (ref "R527") (pin "2") (pinfunction "2_2") (pintype "passive"))
    )
    (net (code "69") (name "Net-(Q52B-C)") (class "Default")
      (node (ref "C510") (pin "1") (pinfunction "1_1") (pintype "passive"))
      (node (ref "C511") (pin "1") (pinfunction "1_1") (pintype "passive"))
      (node (ref "Q52") (pin "3") (pinfunction "C_3") (pintype "passive"))
      (node (ref "R522") (pin "1") (pinfunction "1_1") (pintype "passive"))
      (node (ref "R523") (pin "2") (pinfunction "2_2") (pintype "passive"))
    )
    (net (code "70") (name "Net-(Q52B-E)") (class "Default")
      (node (ref "Q52") (pin "4") (pinfunction "E_4") (pintype "passive"))
      (node (ref "R528") (pin "2") (pinfunction "2_2") (pintype "passive"))
    )
    (net (code "71") (name "Net-(Q53-Pad1)") (class "Default")
      (node (ref "Q53") (pin "1") (pinfunction "1_1") (pintype "passive"))
      (node (ref "R51") (pin "2") (pinfunction "2_2") (pintype "passive"))
    )
    (net (code "72") (name "Net-(Q54-Pad1)") (class "Default")
      (node (ref "Q54") (pin "1") (pinfunction "1_1") (pintype "passive"))
      (node (ref "R58") (pin "2") (pinfunction "2_2") (pintype "passive"))
    )
    (net (code "73") (name "Net-(Q55-Pad1)") (class "Default")
      (node (ref "Q55") (pin "1") (pinfunction "1_1") (pintype "passive"))
      (node (ref "R515") (pin "2") (pinfunction "2_2") (pintype "passive"))
    )
    (net (code "74") (name "Net-(Q56-Pad1)") (class "Default")
      (node (ref "Q56") (pin "1") (pinfunction "1_1") (pintype "passive"))
      (node (ref "R522") (pin "2") (pinfunction "2_2") (pintype "passive"))
    )
    (net (code "75") (name "Net-(R24-Pad2)") (class "Default")
      (node (ref "R24") (pin "2") (pinfunction "2_2") (pintype "passive"))
      (node (ref "U23") (pin "1") (pinfunction "1_1") (pintype "passive"))
      (node (ref "U23") (pin "2") (pinfunction "2_2") (pintype "passive"))
    )
    (net (code "76") (name "Net-(R25-Pad1)") (class "Default")
      (node (ref "R25") (pin "1") (pinfunction "1_1") (pintype "passive"))
      (node (ref "U24") (pin "4") (pinfunction "4_4") (pintype "passive"))
    )
    (net (code "77") (name "Net-(R53-Pad1)") (class "Default")
      (node (ref "R53") (pin "1") (pinfunction "1_1") (pintype "passive"))
      (node (ref "R54") (pin "2") (pinfunction "2_2") (pintype "passive"))
      (node (ref "R55") (pin "1") (pinfunction "1_1") (pintype "passive"))
    )
    (net (code "78") (name "Net-(R61-Pad1)") (class "Default")
      (node (ref "R61") (pin "1") (pinfunction "1_1") (pintype "passive"))
      (node (ref "R62") (pin "2") (pinfunction "2_2") (pintype "passive"))
      (node (ref "U61") (pin "6") (pinfunction "6_6") (pintype "passive"))
    )
    (net (code "79") (name "Net-(R510-Pad1)") (class "Default")
      (node (ref "R510") (pin "1") (pinfunction "1_1") (pintype "passive"))
      (node (ref "R511") (pin "2") (pinfunction "2_2") (pintype "passive"))
      (node (ref "R512") (pin "1") (pinfunction "1_1") (pintype "passive"))
    )
    (net (code "80") (name "Net-(R517-Pad1)") (class "Default")
      (node (ref "R517") (pin "1") (pinfunction "1_1") (pintype "passive"))
      (node (ref "R518") (pin "2") (pinfunction "2_2") (pintype "passive"))
      (node (ref "R519") (pin "1") (pinfunction "1_1") (pintype "passive"))
    )
    (net (code "81") (name "Net-(R524-Pad1)") (class "Default")
      (node (ref "R524") (pin "1") (pinfunction "1_1") (pintype "passive"))
      (node (ref "R525") (pin "2") (pinfunction "2_2") (pintype "passive"))
      (node (ref "R526") (pin "1") (pinfunction "1_1") (pintype "passive"))
    )
    (net (code "82") (name "Net-(U21-A0)") (class "Default")
      (node (ref "R21") (pin "1") (pinfunction "1_1") (pintype "passive"))
      (node (ref "U21") (pin "11") (pinfunction "A0_11") (pintype "input"))
      (node (ref "U22") (pin "11") (pinfunction "A0_11") (pintype "input"))
    )
    (net (code "83") (name "Net-(U21-A1)") (class "Default")
      (node (ref "R22") (pin "1") (pinfunction "1_1") (pintype "passive"))
      (node (ref "U21") (pin "10") (pinfunction "A1_10") (pintype "input"))
      (node (ref "U22") (pin "10") (pinfunction "A1_10") (pintype "input"))
    )
    (net (code "84") (name "Net-(U21-A2)") (class "Default")
      (node (ref "R23") (pin "1") (pinfunction "1_1") (pintype "passive"))
      (node (ref "U21") (pin "9") (pinfunction "A2_9") (pintype "input"))
      (node (ref "U22") (pin "9") (pinfunction "A2_9") (pintype "input"))
    )
    (net (code "85") (name "Net-(U31-VIN)") (class "Default")
      (node (ref "C31") (pin "2") (pinfunction "2_2") (pintype "passive"))
      (node (ref "R31") (pin "1") (pinfunction "1_1") (pintype "passive"))
      (node (ref "R32") (pin "2") (pinfunction "2_2") (pintype "passive"))
      (node (ref "U31") (pin "3") (pinfunction "VIN_3") (pintype "input"))
    )
    (net (code "86") (name "unconnected-(J11-Pad2)") (class "Default")
      (node (ref "J11") (pin "2") (pinfunction "2_2") (pintype "passive+no_connect"))
    )
    (net (code "87") (name "unconnected-(J11-Pad4)") (class "Default")
      (node (ref "J11") (pin "4") (pinfunction "4_4") (pintype "passive+no_connect"))
    )
    (net (code "88") (name "unconnected-(J11-Pad6)") (class "Default")
      (node (ref "J11") (pin "6") (pinfunction "6_6") (pintype "passive+no_connect"))
    )
    (net (code "89") (name "unconnected-(J11-Pad8)") (class "Default")
      (node (ref "J11") (pin "8") (pinfunction "8_8") (pintype "passive+no_connect"))
    )
    (net (code "90") (name "unconnected-(J11-Pad9)") (class "Default")
      (node (ref "J11") (pin "9") (pinfunction "9_9") (pintype "passive+no_connect"))
    )
    (net (code "91") (name "unconnected-(J11-Pad11)") (class "Default")
      (node (ref "J11") (pin "11") (pinfunction "11_11") (pintype "passive+no_connect"))
    )
    (net (code "92") (name "unconnected-(J11-Pad17)") (class "Default")
      (node (ref "J11") (pin "17") (pinfunction "17_17") (pintype "passive+no_connect"))
    )
    (net (code "93") (name "unconnected-(J11-Pad19)") (class "Default")
      (node (ref "J11") (pin "19") (pinfunction "19_19") (pintype "passive+no_connect"))
    )
    (net (code "94") (name "unconnected-(J14-Pad6)") (class "Default")
      (node (ref "J14") (pin "6") (pinfunction "6_6") (pintype "passive+no_connect"))
    )
    (net (code "95") (name "unconnected-(J14-Pad12)") (class "Default")
      (node (ref "J14") (pin "12") (pinfunction "12_12") (pintype "passive+no_connect"))
    )
    (net (code "96") (name "unconnected-(J26-Pad6)") (class "Default")
      (node (ref "J26") (pin "6") (pinfunction "6_6") (pintype "passive+no_connect"))
    )
    (net (code "97") (name "unconnected-(J26-Pad12)") (class "Default")
      (node (ref "J26") (pin "12") (pinfunction "12_12") (pintype "passive+no_connect"))
    )
    (net (code "98") (name "unconnected-(J34-Pad6)") (class "Default")
      (node (ref "J34") (pin "6") (pinfunction "6_6") (pintype "passive+no_connect"))
    )
    (net (code "99") (name "unconnected-(J34-Pad10)") (class "Default")
      (node (ref "J34") (pin "10") (pinfunction "10_10") (pintype "passive+no_connect"))
    )
    (net (code "100") (name "unconnected-(J34-Pad12)") (class "Default")
      (node (ref "J34") (pin "12") (pinfunction "12_12") (pintype "passive+no_connect"))
    )
    (net (code "101") (name "unconnected-(U21-NC-Pad7)") (class "Default")
      (node (ref "U21") (pin "7") (pinfunction "NC_7") (pintype "power_in+no_connect"))
    )
    (net (code "102") (name "unconnected-(U21-S5-Pad5)") (class "Default")
      (node (ref "U21") (pin "5") (pinfunction "S5_5") (pintype "bidirectional+no_connect"))
    )
    (net (code "103") (name "unconnected-(U21-S6-Pad2)") (class "Default")
      (node (ref "U21") (pin "2") (pinfunction "S6_2") (pintype "bidirectional+no_connect"))
    )
    (net (code "104") (name "unconnected-(U21-S7-Pad4)") (class "Default")
      (node (ref "U21") (pin "4") (pinfunction "S7_4") (pintype "bidirectional+no_connect"))
    )
    (net (code "105") (name "unconnected-(U22-NC-Pad7)") (class "Default")
      (node (ref "U22") (pin "7") (pinfunction "NC_7") (pintype "power_in+no_connect"))
    )
    (net (code "106") (name "unconnected-(U22-S5-Pad5)") (class "Default")
      (node (ref "U22") (pin "5") (pinfunction "S5_5") (pintype "bidirectional+no_connect"))
    )
    (net (code "107") (name "unconnected-(U22-S6-Pad2)") (class "Default")
      (node (ref "U22") (pin "2") (pinfunction "S6_2") (pintype "bidirectional+no_connect"))
    )
    (net (code "108") (name "unconnected-(U22-S7-Pad4)") (class "Default")
      (node (ref "U22") (pin "4") (pinfunction "S7_4") (pintype "bidirectional+no_connect"))
    )
    (net (code "109") (name "unconnected-(U61-Pad5)") (class "Default")
      (node (ref "U61") (pin "5") (pinfunction "5_5") (pintype "passive+no_connect"))
    )
  )
)
